# DDS_RIKEN_main.net
KiCad netlist of a schematic drawn in Altium Designer
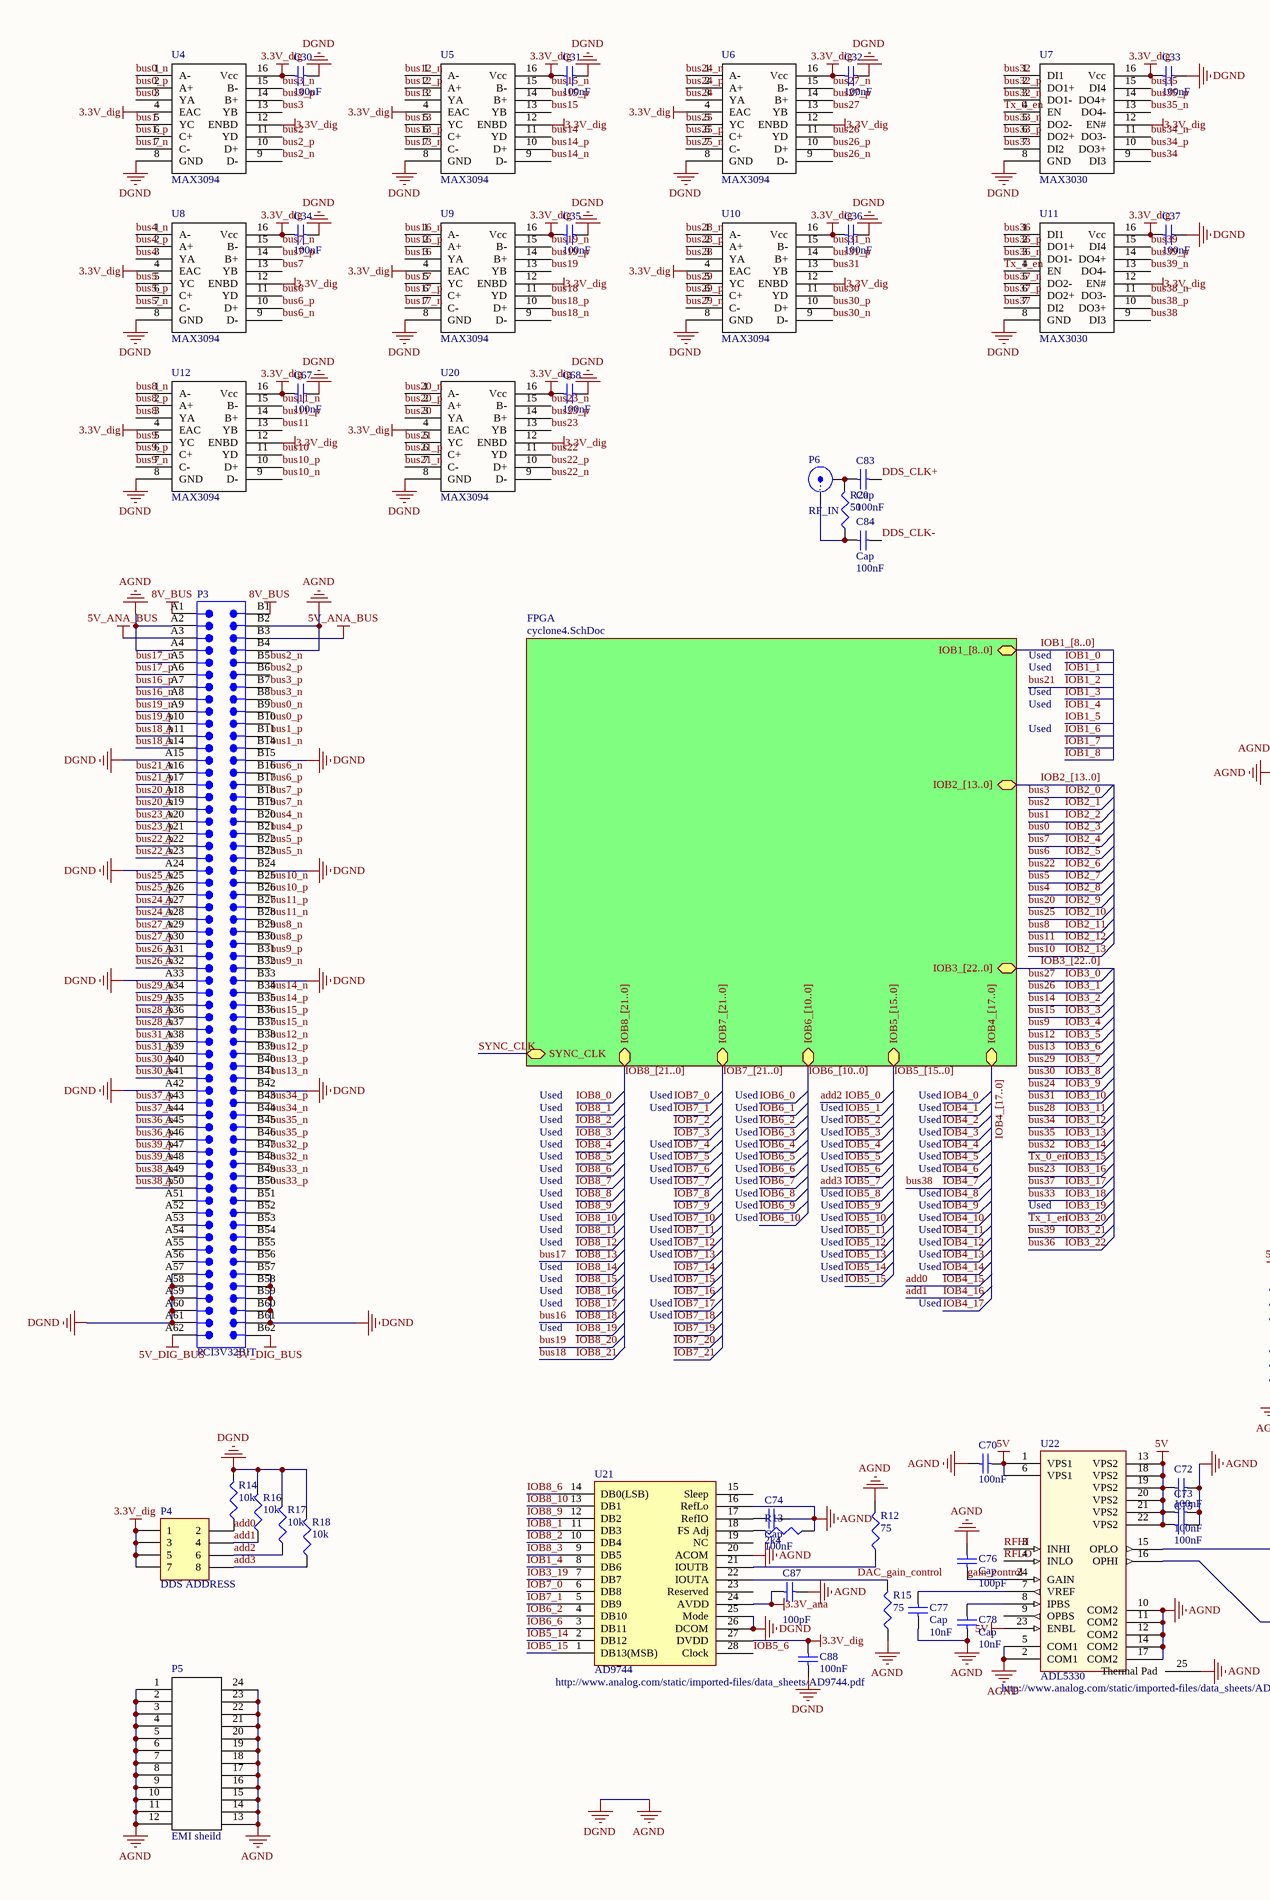
[diagram p0: DDS_RIKEN_main.SchDoc, left]
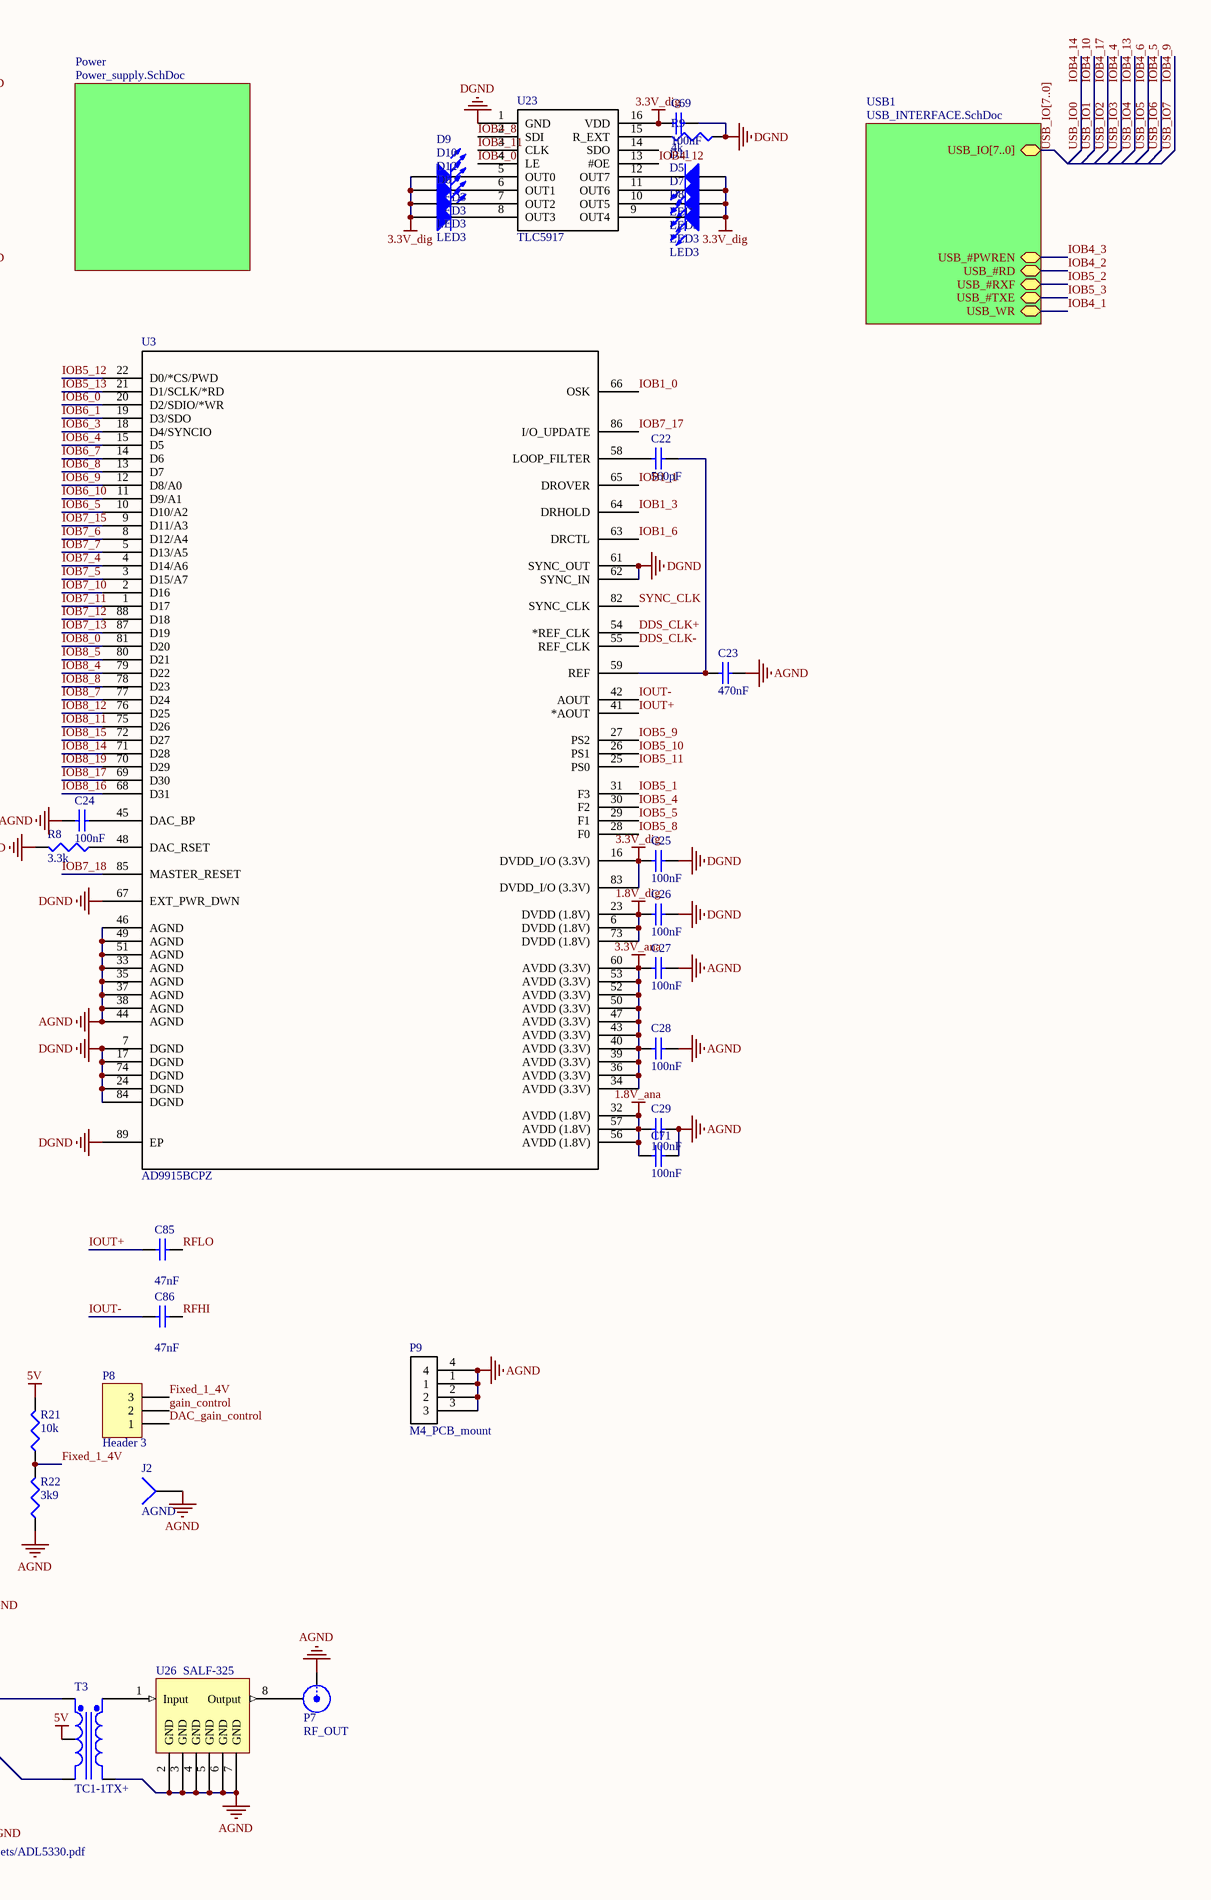
[diagram p1: DDS_RIKEN_main.SchDoc, right]

(export (version "E")
  (design (tool "Eeschema 10.0.6"))
  (components
    (comp (ref "C22")
      (value "560pF")
      (footprint "CAPC2012L")
      (description "Capacitor (Semiconductor SIM Model)")
      (fields (field (name "Comment") "Cap Semi") (field (name "PUBLISHER") "Altium Limited"))
      (libsource (lib "Miscellaneous Devices") (part "Cap Semi"))
    )
    (comp (ref "C23")
      (value "470nF")
      (footprint "CAPC2012L")
      (description "Capacitor (Semiconductor SIM Model)")
      (fields (field (name "Comment") "Cap Semi") (field (name "PUBLISHER") "Altium Limited"))
      (libsource (lib "Miscellaneous Devices") (part "Cap Semi"))
    )
    (comp (ref "C24")
      (value "100nF")
      (footprint "CAPC2012L")
      (description "Capacitor (Semiconductor SIM Model)")
      (fields (field (name "Comment") "Cap Semi") (field (name "PUBLISHER") "Altium Limited"))
      (libsource (lib "Miscellaneous Devices") (part "Cap Semi"))
    )
    (comp (ref "C25")
      (value "100nF")
      (footprint "CAPC2012L")
      (description "Capacitor (Semiconductor SIM Model)")
      (fields (field (name "Comment") "Cap Semi") (field (name "PUBLISHER") "Altium Limited"))
      (libsource (lib "Miscellaneous Devices") (part "Cap Semi"))
    )
    (comp (ref "C26")
      (value "100nF")
      (footprint "CAPC2012L")
      (description "Capacitor (Semiconductor SIM Model)")
      (fields (field (name "Comment") "Cap Semi") (field (name "PUBLISHER") "Altium Limited"))
      (libsource (lib "Miscellaneous Devices") (part "Cap Semi"))
    )
    (comp (ref "C27")
      (value "100nF")
      (footprint "CAPC2012L")
      (description "Capacitor (Semiconductor SIM Model)")
      (fields (field (name "Comment") "Cap Semi") (field (name "PUBLISHER") "Altium Limited"))
      (libsource (lib "Miscellaneous Devices") (part "Cap Semi"))
    )
    (comp (ref "C28")
      (value "100nF")
      (footprint "CAPC2012L")
      (description "Capacitor (Semiconductor SIM Model)")
      (fields (field (name "Comment") "Cap Semi") (field (name "PUBLISHER") "Altium Limited"))
      (libsource (lib "Miscellaneous Devices") (part "Cap Semi"))
    )
    (comp (ref "C29")
      (value "100nF")
      (footprint "CAPC2012L")
      (description "Capacitor (Semiconductor SIM Model)")
      (fields (field (name "Comment") "Cap Semi") (field (name "PUBLISHER") "Altium Limited"))
      (libsource (lib "Miscellaneous Devices") (part "Cap Semi"))
    )
    (comp (ref "C30")
      (value "100nF")
      (footprint "CAPC2012L")
      (description "Capacitor (Semiconductor SIM Model)")
      (fields (field (name "Comment") "Cap Semi") (field (name "PUBLISHER") "Altium Limited"))
      (libsource (lib "Miscellaneous Devices") (part "Cap Semi"))
    )
    (comp (ref "C31")
      (value "100nF")
      (footprint "CAPC2012L")
      (description "Capacitor (Semiconductor SIM Model)")
      (fields (field (name "Comment") "Cap Semi") (field (name "PUBLISHER") "Altium Limited"))
      (libsource (lib "Miscellaneous Devices") (part "Cap Semi"))
    )
    (comp (ref "C32")
      (value "100nF")
      (footprint "CAPC2012L")
      (description "Capacitor (Semiconductor SIM Model)")
      (fields (field (name "Comment") "Cap Semi") (field (name "PUBLISHER") "Altium Limited"))
      (libsource (lib "Miscellaneous Devices") (part "Cap Semi"))
    )
    (comp (ref "C33")
      (value "100nF")
      (footprint "CAPC2012L")
      (description "Capacitor (Semiconductor SIM Model)")
      (fields (field (name "Comment") "Cap Semi") (field (name "PUBLISHER") "Altium Limited"))
      (libsource (lib "Miscellaneous Devices") (part "Cap Semi"))
    )
    (comp (ref "C34")
      (value "100nF")
      (footprint "CAPC2012L")
      (description "Capacitor (Semiconductor SIM Model)")
      (fields (field (name "Comment") "Cap Semi") (field (name "PUBLISHER") "Altium Limited"))
      (libsource (lib "Miscellaneous Devices") (part "Cap Semi"))
    )
    (comp (ref "C35")
      (value "100nF")
      (footprint "CAPC2012L")
      (description "Capacitor (Semiconductor SIM Model)")
      (fields (field (name "Comment") "Cap Semi") (field (name "PUBLISHER") "Altium Limited"))
      (libsource (lib "Miscellaneous Devices") (part "Cap Semi"))
    )
    (comp (ref "C36")
      (value "100nF")
      (footprint "CAPC2012L")
      (description "Capacitor (Semiconductor SIM Model)")
      (fields (field (name "Comment") "Cap Semi") (field (name "PUBLISHER") "Altium Limited"))
      (libsource (lib "Miscellaneous Devices") (part "Cap Semi"))
    )
    (comp (ref "C37")
      (value "100nF")
      (footprint "CAPC2012L")
      (description "Capacitor (Semiconductor SIM Model)")
      (fields (field (name "Comment") "Cap Semi") (field (name "PUBLISHER") "Altium Limited"))
      (libsource (lib "Miscellaneous Devices") (part "Cap Semi"))
    )
    (comp (ref "C67")
      (value "100nF")
      (footprint "CAPC2012L")
      (description "Capacitor (Semiconductor SIM Model)")
      (fields (field (name "Comment") "Cap Semi") (field (name "PUBLISHER") "Altium Limited"))
      (libsource (lib "Miscellaneous Devices") (part "Cap Semi"))
    )
    (comp (ref "C68")
      (value "100nF")
      (footprint "CAPC2012L")
      (description "Capacitor (Semiconductor SIM Model)")
      (fields (field (name "Comment") "Cap Semi") (field (name "PUBLISHER") "Altium Limited"))
      (libsource (lib "Miscellaneous Devices") (part "Cap Semi"))
    )
    (comp (ref "C69")
      (value "100nF")
      (footprint "CAPC2012L")
      (description "Capacitor (Semiconductor SIM Model)")
      (fields (field (name "Comment") "Cap Semi") (field (name "PUBLISHER") "Altium Limited"))
      (libsource (lib "Miscellaneous Devices") (part "Cap Semi"))
    )
    (comp (ref "C70")
      (value "100nF")
      (footprint "CAPC2012L")
      (description "Capacitor (Semiconductor SIM Model)")
      (fields (field (name "Comment") "Cap Semi") (field (name "PUBLISHER") "Altium Limited"))
      (libsource (lib "Miscellaneous Devices") (part "Cap Semi"))
    )
    (comp (ref "C71")
      (value "100nF")
      (footprint "CAPC2012L")
      (description "Capacitor (Semiconductor SIM Model)")
      (fields (field (name "Comment") "Cap Semi") (field (name "PUBLISHER") "Altium Limited"))
      (libsource (lib "Miscellaneous Devices") (part "Cap Semi"))
    )
    (comp (ref "C72")
      (value "100nF")
      (footprint "CAPC2012L")
      (description "Capacitor (Semiconductor SIM Model)")
      (fields (field (name "Comment") "Cap Semi") (field (name "PUBLISHER") "Altium Limited"))
      (libsource (lib "Miscellaneous Devices") (part "Cap Semi"))
    )
    (comp (ref "C73")
      (value "100nF")
      (footprint "CAPC2012L")
      (description "Capacitor (Semiconductor SIM Model)")
      (fields (field (name "Comment") "Cap Semi") (field (name "PUBLISHER") "Altium Limited"))
      (libsource (lib "Miscellaneous Devices") (part "Cap Semi"))
    )
    (comp (ref "C74")
      (value "Cap")
      (footprint "c0805")
      (description "Capacitor")
      (fields
        (field (name "ALTIUM_VALUE") "100nF")
        (field (name "VOLTAGE") "16V")
        (field (name "PUBLISHER") "Altium Limited")
      )
      (libsource (lib "Miscellaneous Devices") (part "Cap"))
    )
    (comp (ref "C75")
      (value "100nF")
      (footprint "CAPC2012L")
      (description "Capacitor (Semiconductor SIM Model)")
      (fields (field (name "Comment") "Cap Semi") (field (name "PUBLISHER") "Altium Limited"))
      (libsource (lib "Miscellaneous Devices") (part "Cap Semi"))
    )
    (comp (ref "C76")
      (value "Cap")
      (footprint "c0805")
      (description "Capacitor")
      (fields
        (field (name "ALTIUM_VALUE") "100pF")
        (field (name "VOLTAGE") "16V")
        (field (name "PUBLISHER") "Altium Limited")
      )
      (libsource (lib "Miscellaneous Devices") (part "Cap"))
    )
    (comp (ref "C77")
      (value "Cap")
      (footprint "c0805")
      (description "Capacitor")
      (fields
        (field (name "ALTIUM_VALUE") "10nF")
        (field (name "VOLTAGE") "16V")
        (field (name "PUBLISHER") "Altium Limited")
      )
      (libsource (lib "Miscellaneous Devices") (part "Cap"))
    )
    (comp (ref "C78")
      (value "Cap")
      (footprint "c0805")
      (description "Capacitor")
      (fields
        (field (name "ALTIUM_VALUE") "10nF")
        (field (name "VOLTAGE") "16V")
        (field (name "PUBLISHER") "Altium Limited")
      )
      (libsource (lib "Miscellaneous Devices") (part "Cap"))
    )
    (comp (ref "C83")
      (value "Cap")
      (footprint "c0805")
      (description "Capacitor")
      (fields
        (field (name "ALTIUM_VALUE") "100nF")
        (field (name "VOLTAGE") "16V")
        (field (name "PUBLISHER") "Altium Limited")
      )
      (libsource (lib "Miscellaneous Devices") (part "Cap"))
    )
    (comp (ref "C84")
      (value "Cap")
      (footprint "c0805")
      (description "Capacitor")
      (fields
        (field (name "ALTIUM_VALUE") "100nF")
        (field (name "VOLTAGE") "16V")
        (field (name "PUBLISHER") "Altium Limited")
      )
      (libsource (lib "Miscellaneous Devices") (part "Cap"))
    )
    (comp (ref "C85")
      (value "47nF")
      (footprint "c0805")
      (description "Capacitor")
      (fields
        (field (name "VOLTAGE") "16V")
        (field (name "Comment") "Cap")
        (field (name "PUBLISHER") "Altium Limited")
      )
      (libsource (lib "Miscellaneous Devices") (part "Cap"))
    )
    (comp (ref "C86")
      (value "47nF")
      (footprint "c0805")
      (description "Capacitor")
      (fields
        (field (name "VOLTAGE") "16V")
        (field (name "Comment") "Cap")
        (field (name "PUBLISHER") "Altium Limited")
      )
      (libsource (lib "Miscellaneous Devices") (part "Cap"))
    )
    (comp (ref "C87")
      (value "100pF")
      (footprint "c0805")
      (description "Capacitor")
      (fields
        (field (name "VOLTAGE") "16V")
        (field (name "Comment") "Cap")
        (field (name "PUBLISHER") "Altium Limited")
      )
      (libsource (lib "Miscellaneous Devices") (part "Cap"))
    )
    (comp (ref "C88")
      (value "100nF")
      (footprint "c0805")
      (description "Capacitor")
      (fields
        (field (name "VOLTAGE") "16V")
        (field (name "Comment") "Cap")
        (field (name "PUBLISHER") "Altium Limited")
      )
      (libsource (lib "Miscellaneous Devices") (part "Cap"))
    )
    (comp (ref "D5")
      (value "LED3")
      (footprint "DSO-C2/D5.6")
      (description "Typical BLUE SiC LED")
      (fields (field (name "PUBLISHER") "Altium Limited"))
      (libsource (lib "Miscellaneous Devices") (part "LED3"))
    )
    (comp (ref "D6")
      (value "LED3")
      (footprint "DSO-C2/D5.6")
      (description "Typical BLUE SiC LED")
      (fields (field (name "PUBLISHER") "Altium Limited"))
      (libsource (lib "Miscellaneous Devices") (part "LED3"))
    )
    (comp (ref "D7")
      (value "LED3")
      (footprint "DSO-C2/D5.6")
      (description "Typical BLUE SiC LED")
      (fields (field (name "PUBLISHER") "Altium Limited"))
      (libsource (lib "Miscellaneous Devices") (part "LED3"))
    )
    (comp (ref "D8")
      (value "LED3")
      (footprint "DSO-C2/D5.6")
      (description "Typical BLUE SiC LED")
      (fields (field (name "PUBLISHER") "Altium Limited"))
      (libsource (lib "Miscellaneous Devices") (part "LED3"))
    )
    (comp (ref "D9")
      (value "LED3")
      (footprint "DSO-C2/D5.6")
      (description "Typical BLUE SiC LED")
      (fields (field (name "PUBLISHER") "Altium Limited"))
      (libsource (lib "Miscellaneous Devices") (part "LED3"))
    )
    (comp (ref "D10")
      (value "LED3")
      (footprint "DSO-C2/D5.6")
      (description "Typical BLUE SiC LED")
      (fields (field (name "PUBLISHER") "Altium Limited"))
      (libsource (lib "Miscellaneous Devices") (part "LED3"))
    )
    (comp (ref "D11")
      (value "LED3")
      (footprint "DSO-C2/D5.6")
      (description "Typical BLUE SiC LED")
      (fields (field (name "PUBLISHER") "Altium Limited"))
      (libsource (lib "Miscellaneous Devices") (part "LED3"))
    )
    (comp (ref "D12")
      (value "LED3")
      (footprint "DSO-C2/D5.6")
      (description "Typical BLUE SiC LED")
      (fields (field (name "PUBLISHER") "Altium Limited"))
      (libsource (lib "Miscellaneous Devices") (part "LED3"))
    )
    (comp (ref "J2")
      (value "AGND")
      (footprint "PIN1")
      (description "Socket")
      (fields (field (name "PUBLISHER") "Altium Limited"))
      (libsource (lib "Miscellaneous Connectors") (part "Socket"))
    )
    (comp (ref "P3")
      (value "PCI3V32BIT")
      (footprint "PCI3V32BIT")
      (description "Card, 120-Position")
      (libsource (lib "*") (part "PCI3V32BIT"))
    )
    (comp (ref "P4")
      (value "DDS ADDRESS")
      (footprint "HDR2X4")
      (description "Header, 4-Pin, Dual row")
      (fields (field (name "PUBLISHER") "Altium Limited"))
      (libsource (lib "Miscellaneous Connectors") (part "Header 4X2"))
    )
    (comp (ref "P5")
      (value "EMI sheild")
      (footprint "BMIS-207")
      (description "Laird Shield")
      (fields (field (name "PUBLISHER") "Altium Limited"))
      (libsource (lib "HH_chips") (part "BMIS-207"))
    )
    (comp (ref "P6")
      (value "RF_IN")
      (footprint "SMA_Edgecon_31milthick")
      (description "SMA Straight Connector")
      (fields (field (name "PUBLISHER") "Altium Limited"))
      (libsource (lib "Miscellaneous Connectors") (part "SMB"))
    )
    (comp (ref "P7")
      (value "RF_OUT")
      (footprint "SMA_Edgecon_31milthick")
      (description "SMA Straight Connector")
      (fields (field (name "PUBLISHER") "Altium Limited"))
      (libsource (lib "Miscellaneous Connectors") (part "SMB"))
    )
    (comp (ref "P8")
      (value "Header 3")
      (footprint "HDR1X3")
      (description "Header, 3-Pin")
      (fields (field (name "PUBLISHER") "Altium Limited"))
      (libsource (lib "Miscellaneous Connectors") (part "Header 3"))
    )
    (comp (ref "P9")
      (value "M4_PCB_mount")
      (footprint "M4_PCB_mount")
      (libsource (lib "HH_chips") (part "M4_PCB_mount"))
    )
    (comp (ref "R8")
      (value "3.3k")
      (footprint "RESC3216L")
      (description "Resistor")
      (fields (field (name "PUBLISHER") "Altium Limited"))
      (libsource (lib "Miscellaneous Devices") (part "Res3"))
    )
    (comp (ref "R9")
      (value "4k")
      (footprint "RESC3216L")
      (description "Resistor")
      (fields (field (name "PUBLISHER") "Altium Limited"))
      (libsource (lib "Miscellaneous Devices") (part "Res3"))
    )
    (comp (ref "R12")
      (value "75")
      (footprint "RESC3216L")
      (description "Resistor")
      (fields (field (name "PUBLISHER") "Altium Limited"))
      (libsource (lib "Miscellaneous Devices") (part "Res3"))
    )
    (comp (ref "R13")
      (value "2k4")
      (footprint "RESC3216L")
      (description "Resistor")
      (fields (field (name "PUBLISHER") "Altium Limited"))
      (libsource (lib "Miscellaneous Devices") (part "Res3"))
    )
    (comp (ref "R14")
      (value "10k")
      (footprint "RESC3216L")
      (description "Resistor")
      (fields (field (name "PUBLISHER") "Altium Limited"))
      (libsource (lib "Miscellaneous Devices") (part "Res3"))
    )
    (comp (ref "R15")
      (value "75")
      (footprint "RESC3216L")
      (description "Resistor")
      (fields (field (name "PUBLISHER") "Altium Limited"))
      (libsource (lib "Miscellaneous Devices") (part "Res3"))
    )
    (comp (ref "R16")
      (value "10k")
      (footprint "RESC3216L")
      (description "Resistor")
      (fields (field (name "PUBLISHER") "Altium Limited"))
      (libsource (lib "Miscellaneous Devices") (part "Res3"))
    )
    (comp (ref "R17")
      (value "10k")
      (footprint "RESC3216L")
      (description "Resistor")
      (fields (field (name "PUBLISHER") "Altium Limited"))
      (libsource (lib "Miscellaneous Devices") (part "Res3"))
    )
    (comp (ref "R18")
      (value "10k")
      (footprint "RESC3216L")
      (description "Resistor")
      (fields (field (name "PUBLISHER") "Altium Limited"))
      (libsource (lib "Miscellaneous Devices") (part "Res3"))
    )
    (comp (ref "R20")
      (value "50")
      (footprint "RESC3216L")
      (description "Resistor")
      (fields (field (name "PUBLISHER") "Altium Limited"))
      (libsource (lib "Miscellaneous Devices") (part "Res3"))
    )
    (comp (ref "R21")
      (value "10k")
      (footprint "RESC3216L")
      (description "Resistor")
      (fields (field (name "PUBLISHER") "Altium Limited"))
      (libsource (lib "Miscellaneous Devices") (part "Res3"))
    )
    (comp (ref "R22")
      (value "3k9")
      (footprint "RESC3216L")
      (description "Resistor")
      (fields (field (name "PUBLISHER") "Altium Limited"))
      (libsource (lib "Miscellaneous Devices") (part "Res3"))
    )
    (comp (ref "T3")
      (value "TC1-1TX+")
      (footprint "TC1-1T+")
      (description "Center-Tapped Transformer (Coupled Inductor Model)")
      (fields (field (name "PUBLISHER") "Altium Limited"))
      (libsource (lib "Miscellaneous Devices") (part "Trans CT"))
    )
    (comp (ref "U3")
      (value "AD9915BCPZ")
      (footprint "CP_88_5")
      (description "Imported")
      (libsource (lib "2014-10-16_14-30-18") (part "AD9915BCPZ"))
    )
    (comp (ref "U4")
      (value "MAX3094")
      (footprint "TSSOP16")
      (description "Differential Line Receivers")
      (libsource (lib "HH_chips") (part "MAX3094"))
    )
    (comp (ref "U5")
      (value "MAX3094")
      (footprint "TSSOP16")
      (description "Differential Line Receivers")
      (libsource (lib "HH_chips") (part "MAX3094"))
    )
    (comp (ref "U6")
      (value "MAX3094")
      (footprint "TSSOP16")
      (description "Differential Line Receivers")
      (libsource (lib "HH_chips") (part "MAX3094"))
    )
    (comp (ref "U7")
      (value "MAX3030")
      (footprint "TSSOP16")
      (description "Differential Line Transmitter")
      (libsource (lib "HH_chips") (part "MAX3030"))
    )
    (comp (ref "U8")
      (value "MAX3094")
      (footprint "TSSOP16")
      (description "Differential Line Receivers")
      (libsource (lib "HH_chips") (part "MAX3094"))
    )
    (comp (ref "U9")
      (value "MAX3094")
      (footprint "TSSOP16")
      (description "Differential Line Receivers")
      (libsource (lib "HH_chips") (part "MAX3094"))
    )
    (comp (ref "U10")
      (value "MAX3094")
      (footprint "TSSOP16")
      (description "Differential Line Receivers")
      (libsource (lib "HH_chips") (part "MAX3094"))
    )
    (comp (ref "U11")
      (value "MAX3030")
      (footprint "TSSOP16")
      (description "Differential Line Transmitter")
      (libsource (lib "HH_chips") (part "MAX3030"))
    )
    (comp (ref "U12")
      (value "MAX3094")
      (footprint "TSSOP16")
      (description "Differential Line Receivers")
      (libsource (lib "HH_chips") (part "MAX3094"))
    )
    (comp (ref "U20")
      (value "MAX3094")
      (footprint "TSSOP16")
      (description "Differential Line Receivers")
      (libsource (lib "HH_chips") (part "MAX3094"))
    )
    (comp (ref "U21")
      (value "AD9744")
      (footprint "TSOP65P640-28AM")
      (fields (field (name "HELPURL") "http://www.analog.com/static/imported-files/data_sheets/AD9744.pdf"))
      (libsource (lib "eigene") (part "AD9744"))
    )
    (comp (ref "U22")
      (value "ADL5330")
      (footprint "QFN50P400X400-24VAN")
      (description "analoger Abschwächer")
      (fields (field (name "HELPURL") "http://www.analog.com/static/imported-files/data_sheets/ADL5330.pdf"))
      (libsource (lib "eigene") (part "ADL5330"))
    )
    (comp (ref "U23")
      (value "TLC5917")
      (footprint "D016_N")
      (description "8-bit LED driver (Serial)")
      (libsource (lib "HH_chips") (part "TLC5917"))
    )
    (comp (ref "U26")
      (value "SALF-325")
      (footprint "SALF-325")
      (libsource (lib "Mini-Circuits") (part "SALF-325"))
    )
  )
  (nets
    (net (code "1") (name "/DAC_gain_control") (class "Default")
      (node (ref "P8") (pin "1") (pinfunction "1_1") (pintype "passive"))
      (node (ref "R15") (pin "2") (pinfunction "2_2") (pintype "passive"))
      (node (ref "U21") (pin "22") (pinfunction "IOUTA_22") (pintype "power_in"))
    )
    (net (code "2") (name "/DDS_CLK+") (class "Default")
      (node (ref "C83") (pin "1") (pinfunction "1_1") (pintype "passive"))
      (node (ref "U3") (pin "54") (pinfunction "*REF_CLK_54") (pintype "passive"))
    )
    (net (code "3") (name "/DDS_CLK-") (class "Default")
      (node (ref "C84") (pin "1") (pinfunction "1_1") (pintype "passive"))
      (node (ref "U3") (pin "55") (pinfunction "REF_CLK_55") (pintype "passive"))
    )
    (net (code "4") (name "/Fixed_1_4V") (class "Default")
      (node (ref "P8") (pin "3") (pinfunction "3_3") (pintype "passive"))
      (node (ref "R21") (pin "1") (pinfunction "1_1") (pintype "passive"))
      (node (ref "R22") (pin "2") (pinfunction "2_2") (pintype "passive"))
    )
    (net (code "5") (name "/IOB1_0") (class "Default")
      (node (ref "U3") (pin "66") (pinfunction "OSK_66") (pintype "passive"))
    )
    (net (code "6") (name "/IOB1_1") (class "Default")
      (node (ref "U3") (pin "65") (pinfunction "DROVER_65") (pintype "passive"))
    )
    (net (code "7") (name "/IOB1_2") (class "Default")
      (node (ref "U20") (pin "5") (pinfunction "YC_5") (pintype "passive"))
    )
    (net (code "8") (name "/IOB1_3") (class "Default")
      (node (ref "U3") (pin "64") (pinfunction "DRHOLD_64") (pintype "passive"))
    )
    (net (code "9") (name "/IOB1_4") (class "Default")
      (node (ref "U21") (pin "8") (pinfunction "DB6_8") (pintype "power_in"))
    )
    (net (code "11") (name "/IOB1_6") (class "Default")
      (node (ref "U3") (pin "63") (pinfunction "DRCTL_63") (pintype "passive"))
    )
    (net (code "15") (name "/IOB2_0") (class "Default")
      (node (ref "U4") (pin "13") (pinfunction "YB_13") (pintype "passive"))
    )
    (net (code "16") (name "/IOB2_1") (class "Default")
      (node (ref "U4") (pin "11") (pinfunction "YD_11") (pintype "passive"))
    )
    (net (code "17") (name "/IOB2_2") (class "Default")
      (node (ref "U4") (pin "5") (pinfunction "YC_5") (pintype "passive"))
    )
    (net (code "18") (name "/IOB2_3") (class "Default")
      (node (ref "U4") (pin "3") (pinfunction "YA_3") (pintype "passive"))
    )
    (net (code "19") (name "/IOB2_4") (class "Default")
      (node (ref "U8") (pin "13") (pinfunction "YB_13") (pintype "passive"))
    )
    (net (code "20") (name "/IOB2_5") (class "Default")
      (node (ref "U8") (pin "11") (pinfunction "YD_11") (pintype "passive"))
    )
    (net (code "21") (name "/IOB2_6") (class "Default")
      (node (ref "U20") (pin "11") (pinfunction "YD_11") (pintype "passive"))
    )
    (net (code "22") (name "/IOB2_7") (class "Default")
      (node (ref "U8") (pin "5") (pinfunction "YC_5") (pintype "passive"))
    )
    (net (code "23") (name "/IOB2_8") (class "Default")
      (node (ref "U8") (pin "3") (pinfunction "YA_3") (pintype "passive"))
    )
    (net (code "24") (name "/IOB2_9") (class "Default")
      (node (ref "U20") (pin "3") (pinfunction "YA_3") (pintype "passive"))
    )
    (net (code "25") (name "/IOB2_10") (class "Default")
      (node (ref "U6") (pin "5") (pinfunction "YC_5") (pintype "passive"))
    )
    (net (code "26") (name "/IOB2_11") (class "Default")
      (node (ref "U12") (pin "3") (pinfunction "YA_3") (pintype "passive"))
    )
    (net (code "27") (name "/IOB2_12") (class "Default")
      (node (ref "U12") (pin "13") (pinfunction "YB_13") (pintype "passive"))
    )
    (net (code "28") (name "/IOB2_13") (class "Default")
      (node (ref "U12") (pin "11") (pinfunction "YD_11") (pintype "passive"))
    )
    (net (code "30") (name "/IOB3_0") (class "Default")
      (node (ref "U6") (pin "13") (pinfunction "YB_13") (pintype "passive"))
    )
    (net (code "31") (name "/IOB3_1") (class "Default")
      (node (ref "U6") (pin "11") (pinfunction "YD_11") (pintype "passive"))
    )
    (net (code "32") (name "/IOB3_2") (class "Default")
      (node (ref "U5") (pin "11") (pinfunction "YD_11") (pintype "passive"))
    )
    (net (code "33") (name "/IOB3_3") (class "Default")
      (node (ref "U5") (pin "13") (pinfunction "YB_13") (pintype "passive"))
    )
    (net (code "34") (name "/IOB3_4") (class "Default")
      (node (ref "U12") (pin "5") (pinfunction "YC_5") (pintype "passive"))
    )
    (net (code "35") (name "/IOB3_5") (class "Default")
      (node (ref "U5") (pin "3") (pinfunction "YA_3") (pintype "passive"))
    )
    (net (code "36") (name "/IOB3_6") (class "Default")
      (node (ref "U5") (pin "5") (pinfunction "YC_5") (pintype "passive"))
    )
    (net (code "37") (name "/IOB3_7") (class "Default")
      (node (ref "U10") (pin "5") (pinfunction "YC_5") (pintype "passive"))
    )
    (net (code "38") (name "/IOB3_8") (class "Default")
      (node (ref "U10") (pin "11") (pinfunction "YD_11") (pintype "passive"))
    )
    (net (code "39") (name "/IOB3_9") (class "Default")
      (node (ref "U6") (pin "3") (pinfunction "YA_3") (pintype "passive"))
    )
    (net (code "40") (name "/IOB3_10") (class "Default")
      (node (ref "U10") (pin "13") (pinfunction "YB_13") (pintype "passive"))
    )
    (net (code "41") (name "/IOB3_11") (class "Default")
      (node (ref "U10") (pin "3") (pinfunction "YA_3") (pintype "passive"))
    )
    (net (code "42") (name "/IOB3_12") (class "Default")
      (node (ref "U7") (pin "9") (pinfunction "DI3_9") (pintype "passive"))
    )
    (net (code "43") (name "/IOB3_13") (class "Default")
      (node (ref "U7") (pin "15") (pinfunction "DI4_15") (pintype "passive"))
    )
    (net (code "44") (name "/IOB3_14") (class "Default")
      (node (ref "U7") (pin "1") (pinfunction "DI1_1") (pintype "passive"))
    )
    (net (code "45") (name "/IOB3_15") (class "Default")
      (node (ref "U7") (pin "4") (pinfunction "EN_4") (pintype "passive"))
    )
    (net (code "46") (name "/IOB3_16") (class "Default")
      (node (ref "U20") (pin "13") (pinfunction "YB_13") (pintype "passive"))
    )
    (net (code "47") (name "/IOB3_17") (class "Default")
      (node (ref "U11") (pin "7") (pinfunction "DI2_7") (pintype "passive"))
    )
    (net (code "48") (name "/IOB3_18") (class "Default")
      (node (ref "U7") (pin "7") (pinfunction "DI2_7") (pintype "passive"))
    )
    (net (code "49") (name "/IOB3_19") (class "Default")
      (node (ref "U21") (pin "7") (pinfunction "DB7_7") (pintype "power_in"))
    )
    (net (code "50") (name "/IOB3_20") (class "Default")
      (node (ref "U11") (pin "4") (pinfunction "EN_4") (pintype "passive"))
    )
    (net (code "51") (name "/IOB3_21") (class "Default")
      (node (ref "U11") (pin "15") (pinfunction "DI4_15") (pintype "passive"))
    )
    (net (code "52") (name "/IOB3_22") (class "Default")
      (node (ref "U11") (pin "1") (pinfunction "DI1_1") (pintype "passive"))
    )
    (net (code "54") (name "/IOB4_0") (class "Default")
      (node (ref "U23") (pin "4") (pinfunction "LE_4") (pintype "passive"))
    )
    (net (code "58") (name "/IOB4_7") (class "Default")
      (node (ref "U11") (pin "9") (pinfunction "DI3_9") (pintype "passive"))
    )
    (net (code "59") (name "/IOB4_8") (class "Default")
      (node (ref "U23") (pin "2") (pinfunction "SDI_2") (pintype "passive"))
    )
    (net (code "60") (name "/IOB4_11") (class "Default")
      (node (ref "U23") (pin "3") (pinfunction "CLK_3") (pintype "passive"))
    )
    (net (code "61") (name "/IOB4_12") (class "Default")
      (node (ref "U23") (pin "13") (pinfunction "#OE_13") (pintype "passive"))
    )
    (net (code "62") (name "/IOB4_15") (class "Default")
      (node (ref "P4") (pin "2") (pinfunction "2_2") (pintype "passive"))
      (node (ref "R14") (pin "1") (pinfunction "1_1") (pintype "passive"))
    )
    (net (code "63") (name "/IOB4_16") (class "Default")
      (node (ref "P4") (pin "4") (pinfunction "4_4") (pintype "passive"))
      (node (ref "R16") (pin "1") (pinfunction "1_1") (pintype "passive"))
    )
    (net (code "65") (name "/IOB5_0") (class "Default")
      (node (ref "P4") (pin "6") (pinfunction "6_6") (pintype "passive"))
      (node (ref "R17") (pin "1") (pinfunction "1_1") (pintype "passive"))
    )
    (net (code "66") (name "/IOB5_1") (class "Default")
      (node (ref "U3") (pin "31") (pinfunction "F3_31") (pintype "passive"))
    )
    (net (code "69") (name "/IOB5_4") (class "Default")
      (node (ref "U3") (pin "30") (pinfunction "F2_30") (pintype "passive"))
    )
    (net (code "70") (name "/IOB5_5") (class "Default")
      (node (ref "U3") (pin "29") (pinfunction "F1_29") (pintype "passive"))
    )
    (net (code "71") (name "/IOB5_6") (class "Default")
      (node (ref "U21") (pin "28") (pinfunction "Clock_28") (pintype "power_in"))
    )
    (net (code "72") (name "/IOB5_7") (class "Default")
      (node (ref "P4") (pin "8") (pinfunction "8_8") (pintype "passive"))
      (node (ref "R18") (pin "1") (pinfunction "1_1") (pintype "passive"))
    )
    (net (code "73") (name "/IOB5_8") (class "Default")
      (node (ref "U3") (pin "28") (pinfunction "F0_28") (pintype "passive"))
    )
    (net (code "74") (name "/IOB5_9") (class "Default")
      (node (ref "U3") (pin "27") (pinfunction "PS2_27") (pintype "passive"))
    )
    (net (code "75") (name "/IOB5_10") (class "Default")
      (node (ref "U3") (pin "26") (pinfunction "PS1_26") (pintype "passive"))
    )
    (net (code "76") (name "/IOB5_11") (class "Default")
      (node (ref "U3") (pin "25") (pinfunction "PS0_25") (pintype "passive"))
    )
    (net (code "77") (name "/IOB5_12") (class "Default")
      (node (ref "U3") (pin "22") (pinfunction "D0/*CS/PWD_22") (pintype "passive"))
    )
    (net (code "78") (name "/IOB5_13") (class "Default")
      (node (ref "U3") (pin "21") (pinfunction "D1/SCLK/*RD_21") (pintype "passive"))
    )
    (net (code "79") (name "/IOB5_14") (class "Default")
      (node (ref "U21") (pin "2") (pinfunction "DB12_2") (pintype "power_in"))
    )
    (net (code "80") (name "/IOB5_15") (class "Default")
      (node (ref "U21") (pin "1") (pinfunction "DB13(MSB)_1") (pintype "power_in"))
    )
    (net (code "82") (name "/IOB6_0") (class "Default")
      (node (ref "U3") (pin "20") (pinfunction "D2/SDIO/*WR_20") (pintype "passive"))
    )
    (net (code "83") (name "/IOB6_1") (class "Default")
      (node (ref "U3") (pin "19") (pinfunction "D3/SDO_19") (pintype "passive"))
    )
    (net (code "84") (name "/IOB6_2") (class "Default")
      (node (ref "U21") (pin "4") (pinfunction "DB10_4") (pintype "power_in"))
    )
    (net (code "85") (name "/IOB6_3") (class "Default")
      (node (ref "U3") (pin "18") (pinfunction "D4/SYNCIO_18") (pintype "passive"))
    )
    (net (code "86") (name "/IOB6_4") (class "Default")
      (node (ref "U3") (pin "15") (pinfunction "D5_15") (pintype "passive"))
    )
    (net (code "87") (name "/IOB6_5") (class "Default")
      (node (ref "U3") (pin "10") (pinfunction "D10/A2_10") (pintype "passive"))
    )
    (net (code "88") (name "/IOB6_6") (class "Default")
      (node (ref "U21") (pin "3") (pinfunction "DB11_3") (pintype "power_in"))
    )
    (net (code "89") (name "/IOB6_7") (class "Default")
      (node (ref "U3") (pin "14") (pinfunction "D6_14") (pintype "passive"))
    )
    (net (code "90") (name "/IOB6_8") (class "Default")
      (node (ref "U3") (pin "13") (pinfunction "D7_13") (pintype "passive"))
    )
    (net (code "91") (name "/IOB6_9") (class "Default")
      (node (ref "U3") (pin "12") (pinfunction "D8/A0_12") (pintype "passive"))
    )
    (net (code "92") (name "/IOB6_10") (class "Default")
      (node (ref "U3") (pin "11") (pinfunction "D9/A1_11") (pintype "passive"))
    )
    (net (code "94") (name "/IOB7_0") (class "Default")
      (node (ref "U21") (pin "6") (pinfunction "DB8_6") (pintype "power_in"))
    )
    (net (code "95") (name "/IOB7_1") (class "Default")
      (node (ref "U21") (pin "5") (pinfunction "DB9_5") (pintype "power_in"))
    )
    (net (code "98") (name "/IOB7_4") (class "Default")
      (node (ref "U3") (pin "4") (pinfunction "D14/A6_4") (pintype "passive"))
    )
    (net (code "99") (name "/IOB7_5") (class "Default")
      (node (ref "U3") (pin "3") (pinfunction "D15/A7_3") (pintype "passive"))
    )
    (net (code "100") (name "/IOB7_6") (class "Default")
      (node (ref "U3") (pin "8") (pinfunction "D12/A4_8") (pintype "passive"))
    )
    (net (code "101") (name "/IOB7_7") (class "Default")
      (node (ref "U3") (pin "5") (pinfunction "D13/A5_5") (pintype "passive"))
    )
    (net (code "104") (name "/IOB7_10") (class "Default")
      (node (ref "U3") (pin "2") (pinfunction "D16_2") (pintype "passive"))
    )
    (net (code "105") (name "/IOB7_11") (class "Default")
      (node (ref "U3") (pin "1") (pinfunction "D17_1") (pintype "passive"))
    )
    (net (code "106") (name "/IOB7_12") (class "Default")
      (node (ref "U3") (pin "88") (pinfunction "D18_88") (pintype "passive"))
    )
    (net (code "107") (name "/IOB7_13") (class "Default")
      (node (ref "U3") (pin "87") (pinfunction "D19_87") (pintype "passive"))
    )
    (net (code "109") (name "/IOB7_15") (class "Default")
      (node (ref "U3") (pin "9") (pinfunction "D11/A3_9") (pintype "passive"))
    )
    (net (code "111") (name "/IOB7_17") (class "Default")
      (node (ref "U3") (pin "86") (pinfunction "I/O_UPDATE_86") (pintype "passive"))
    )
    (net (code "112") (name "/IOB7_18") (class "Default")
      (node (ref "U3") (pin "85") (pinfunction "MASTER_RESET_85") (pintype "passive"))
    )
    (net (code "117") (name "/IOB8_0") (class "Default")
      (node (ref "U3") (pin "81") (pinfunction "D20_81") (pintype "passive"))
    )
    (net (code "118") (name "/IOB8_1") (class "Default")
      (node (ref "U21") (pin "11") (pinfunction "DB3_11") (pintype "power_in"))
    )
    (net (code "119") (name "/IOB8_2") (class "Default")
      (node (ref "U21") (pin "10") (pinfunction "DB4_10") (pintype "power_in"))
    )
    (net (code "120") (name "/IOB8_3") (class "Default")
      (node (ref "U21") (pin "9") (pinfunction "DB5_9") (pintype "power_in"))
    )
    (net (code "121") (name "/IOB8_4") (class "Default")
      (node (ref "U3") (pin "79") (pinfunction "D22_79") (pintype "passive"))
    )
    (net (code "122") (name "/IOB8_5") (class "Default")
      (node (ref "U3") (pin "80") (pinfunction "D21_80") (pintype "passive"))
    )
    (net (code "123") (name "/IOB8_6") (class "Default")
      (node (ref "U21") (pin "14") (pinfunction "DB0(LSB)_14") (pintype "power_in"))
    )
    (net (code "124") (name "/IOB8_7") (class "Default")
      (node (ref "U3") (pin "77") (pinfunction "D24_77") (pintype "passive"))
    )
    (net (code "125") (name "/IOB8_8") (class "Default")
      (node (ref "U3") (pin "78") (pinfunction "D23_78") (pintype "passive"))
    )
    (net (code "126") (name "/IOB8_9") (class "Default")
      (node (ref "U21") (pin "12") (pinfunction "DB2_12") (pintype "power_in"))
    )
    (net (code "127") (name "/IOB8_10") (class "Default")
      (node (ref "U21") (pin "13") (pinfunction "DB1_13") (pintype "power_in"))
    )
    (net (code "128") (name "/IOB8_11") (class "Default")
      (node (ref "U3") (pin "75") (pinfunction "D26_75") (pintype "passive"))
    )
    (net (code "129") (name "/IOB8_12") (class "Default")
      (node (ref "U3") (pin "76") (pinfunction "D25_76") (pintype "passive"))
    )
    (net (code "130") (name "/IOB8_13") (class "Default")
      (node (ref "U9") (pin "5") (pinfunction "YC_5") (pintype "passive"))
    )
    (net (code "131") (name "/IOB8_14") (class "Default")
      (node (ref "U3") (pin "71") (pinfunction "D28_71") (pintype "passive"))
    )
    (net (code "132") (name "/IOB8_15") (class "Default")
      (node (ref "U3") (pin "72") (pinfunction "D27_72") (pintype "passive"))
    )
    (net (code "133") (name "/IOB8_16") (class "Default")
      (node (ref "U3") (pin "68") (pinfunction "D31_68") (pintype "passive"))
    )
    (net (code "134") (name "/IOB8_17") (class "Default")
      (node (ref "U3") (pin "69") (pinfunction "D30_69") (pintype "passive"))
    )
    (net (code "135") (name "/IOB8_18") (class "Default")
      (node (ref "U9") (pin "3") (pinfunction "YA_3") (pintype "passive"))
    )
    (net (code "136") (name "/IOB8_19") (class "Default")
      (node (ref "U3") (pin "70") (pinfunction "D29_70") (pintype "passive"))
    )
    (net (code "137") (name "/IOB8_20") (class "Default")
      (node (ref "U9") (pin "13") (pinfunction "YB_13") (pintype "passive"))
    )
    (net (code "138") (name "/IOB8_21") (class "Default")
      (node (ref "U9") (pin "11") (pinfunction "YD_11") (pintype "passive"))
    )
    (net (code "140") (name "/IOUT+") (class "Default")
      (node (ref "C85") (pin "2") (pinfunction "2_2") (pintype "passive"))
      (node (ref "U3") (pin "41") (pinfunction "*AOUT_41") (pintype "passive"))
    )
    (net (code "141") (name "/IOUT-") (class "Default")
      (node (ref "C86") (pin "2") (pinfunction "2_2") (pintype "passive"))
      (node (ref "U3") (pin "42") (pinfunction "AOUT_42") (pintype "passive"))
    )
    (net (code "142") (name "/RFHI") (class "Default")
      (node (ref "C86") (pin "1") (pinfunction "1_1") (pintype "passive"))
      (node (ref "U22") (pin "3") (pinfunction "INHI_3") (pintype "input"))
    )
    (net (code "143") (name "/RFLO") (class "Default")
      (node (ref "C85") (pin "1") (pinfunction "1_1") (pintype "passive"))
      (node (ref "U22") (pin "4") (pinfunction "INLO_4") (pintype "input"))
    )
    (net (code "144") (name "/SYNC_CLK") (class "Default")
      (node (ref "U3") (pin "82") (pinfunction "SYNC_CLK_82") (pintype "passive"))
    )
    (net (code "154") (name "/bus0_n") (class "Default")
      (node (ref "P3") (pin "B9") (pinfunction "B9_B9") (pintype "passive"))
      (node (ref "U4") (pin "1") (pinfunction "A-_1") (pintype "passive"))
    )
    (net (code "155") (name "/bus0_p") (class "Default")
      (node (ref "P3") (pin "B10") (pinfunction "B10_B10") (pintype "passive"))
      (node (ref "U4") (pin "2") (pinfunction "A+_2") (pintype "passive"))
    )
    (net (code "156") (name "/bus1_n") (class "Default")
      (node (ref "P3") (pin "B14") (pinfunction "B14_B14") (pintype "passive"))
      (node (ref "U4") (pin "7") (pinfunction "C-_7") (pintype "passive"))
    )
    (net (code "157") (name "/bus1_p") (class "Default")
      (node (ref "P3") (pin "B11") (pinfunction "B11_B11") (pintype "passive"))
      (node (ref "U4") (pin "6") (pinfunction "C+_6") (pintype "passive"))
    )
    (net (code "158") (name "/bus2_n") (class "Default")
      (node (ref "P3") (pin "B5") (pinfunction "B5_B5") (pintype "passive"))
      (node (ref "U4") (pin "9") (pinfunction "D-_9") (pintype "passive"))
    )
    (net (code "159") (name "/bus2_p") (class "Default")
      (node (ref "P3") (pin "B6") (pinfunction "B6_B6") (pintype "passive"))
      (node (ref "U4") (pin "10") (pinfunction "D+_10") (pintype "passive"))
    )
    (net (code "160") (name "/bus3_n") (class "Default")
      (node (ref "P3") (pin "B8") (pinfunction "B8_B8") (pintype "passive"))
      (node (ref "U4") (pin "15") (pinfunction "B-_15") (pintype "passive"))
    )
    (net (code "161") (name "/bus3_p") (class "Default")
      (node (ref "P3") (pin "B7") (pinfunction "B7_B7") (pintype "passive"))
      (node (ref "U4") (pin "14") (pinfunction "B+_14") (pintype "passive"))
    )
    (net (code "162") (name "/bus4_n") (class "Default")
      (node (ref "P3") (pin "B20") (pinfunction "B20_B20") (pintype "passive"))
      (node (ref "U8") (pin "1") (pinfunction "A-_1") (pintype "passive"))
    )
    (net (code "163") (name "/bus4_p") (class "Default")
      (node (ref "P3") (pin "B21") (pinfunction "B21_B21") (pintype "passive"))
      (node (ref "U8") (pin "2") (pinfunction "A+_2") (pintype "passive"))
    )
    (net (code "164") (name "/bus5_n") (class "Default")
      (node (ref "P3") (pin "B23") (pinfunction "B23_B23") (pintype "passive"))
      (node (ref "U8") (pin "7") (pinfunction "C-_7") (pintype "passive"))
    )
    (net (code "165") (name "/bus5_p") (class "Default")
      (node (ref "P3") (pin "B22") (pinfunction "B22_B22") (pintype "passive"))
      (node (ref "U8") (pin "6") (pinfunction "C+_6") (pintype "passive"))
    )
    (net (code "166") (name "/bus6_n") (class "Default")
      (node (ref "P3") (pin "B16") (pinfunction "B16_B16") (pintype "passive"))
      (node (ref "U8") (pin "9") (pinfunction "D-_9") (pintype "passive"))
    )
    (net (code "167") (name "/bus6_p") (class "Default")
      (node (ref "P3") (pin "B17") (pinfunction "B17_B17") (pintype "passive"))
      (node (ref "U8") (pin "10") (pinfunction "D+_10") (pintype "passive"))
    )
    (net (code "168") (name "/bus7_n") (class "Default")
      (node (ref "P3") (pin "B19") (pinfunction "B19_B19") (pintype "passive"))
      (node (ref "U8") (pin "15") (pinfunction "B-_15") (pintype "passive"))
    )
    (net (code "169") (name "/bus7_p") (class "Default")
      (node (ref "P3") (pin "B18") (pinfunction "B18_B18") (pintype "passive"))
      (node (ref "U8") (pin "14") (pinfunction "B+_14") (pintype "passive"))
    )
    (net (code "170") (name "/bus8_n") (class "Default")
      (node (ref "P3") (pin "B29") (pinfunction "B29_B29") (pintype "passive"))
      (node (ref "U12") (pin "1") (pinfunction "A-_1") (pintype "passive"))
    )
    (net (code "171") (name "/bus8_p") (class "Default")
      (node (ref "P3") (pin "B30") (pinfunction "B30_B30") (pintype "passive"))
      (node (ref "U12") (pin "2") (pinfunction "A+_2") (pintype "passive"))
    )
    (net (code "172") (name "/bus9_n") (class "Default")
      (node (ref "P3") (pin "B32") (pinfunction "B32_B32") (pintype "passive"))
      (node (ref "U12") (pin "7") (pinfunction "C-_7") (pintype "passive"))
    )
    (net (code "173") (name "/bus9_p") (class "Default")
      (node (ref "P3") (pin "B31") (pinfunction "B31_B31") (pintype "passive"))
      (node (ref "U12") (pin "6") (pinfunction "C+_6") (pintype "passive"))
    )
    (net (code "174") (name "/bus10_n") (class "Default")
      (node (ref "P3") (pin "B25") (pinfunction "B25_B25") (pintype "passive"))
      (node (ref "U12") (pin "9") (pinfunction "D-_9") (pintype "passive"))
    )
    (net (code "175") (name "/bus10_p") (class "Default")
      (node (ref "P3") (pin "B26") (pinfunction "B26_B26") (pintype "passive"))
      (node (ref "U12") (pin "10") (pinfunction "D+_10") (pintype "passive"))
    )
    (net (code "176") (name "/bus11_n") (class "Default")
      (node (ref "P3") (pin "B28") (pinfunction "B28_B28") (pintype "passive"))
      (node (ref "U12") (pin "15") (pinfunction "B-_15") (pintype "passive"))
    )
    (net (code "177") (name "/bus11_p") (class "Default")
      (node (ref "P3") (pin "B27") (pinfunction "B27_B27") (pintype "passive"))
      (node (ref "U12") (pin "14") (pinfunction "B+_14") (pintype "passive"))
    )
    (net (code "178") (name "/bus12_n") (class "Default")
      (node (ref "P3") (pin "B38") (pinfunction "B38_B38") (pintype "passive"))
      (node (ref "U5") (pin "1") (pinfunction "A-_1") (pintype "passive"))
    )
    (net (code "179") (name "/bus12_p") (class "Default")
      (node (ref "P3") (pin "B39") (pinfunction "B39_B39") (pintype "passive"))
      (node (ref "U5") (pin "2") (pinfunction "A+_2") (pintype "passive"))
    )
    (net (code "180") (name "/bus13_n") (class "Default")
      (node (ref "P3") (pin "B41") (pinfunction "B41_B41") (pintype "passive"))
      (node (ref "U5") (pin "7") (pinfunction "C-_7") (pintype "passive"))
    )
    (net (code "181") (name "/bus13_p") (class "Default")
      (node (ref "P3") (pin "B40") (pinfunction "B40_B40") (pintype "passive"))
      (node (ref "U5") (pin "6") (pinfunction "C+_6") (pintype "passive"))
    )
    (net (code "182") (name "/bus14_n") (class "Default")
      (node (ref "P3") (pin "B34") (pinfunction "B34_B34") (pintype "passive"))
      (node (ref "U5") (pin "9") (pinfunction "D-_9") (pintype "passive"))
    )
    (net (code "183") (name "/bus14_p") (class "Default")
      (node (ref "P3") (pin "B35") (pinfunction "B35_B35") (pintype "passive"))
      (node (ref "U5") (pin "10") (pinfunction "D+_10") (pintype "passive"))
    )
    (net (code "184") (name "/bus15_n") (class "Default")
      (node (ref "P3") (pin "B37") (pinfunction "B37_B37") (pintype "passive"))
      (node (ref "U5") (pin "15") (pinfunction "B-_15") (pintype "passive"))
    )
    (net (code "185") (name "/bus15_p") (class "Default")
      (node (ref "P3") (pin "B36") (pinfunction "B36_B36") (pintype "passive"))
      (node (ref "U5") (pin "14") (pinfunction "B+_14") (pintype "passive"))
    )
    (net (code "186") (name "/bus16_n") (class "Default")
      (node (ref "P3") (pin "A8") (pinfunction "A8_A8") (pintype "passive"))
      (node (ref "U9") (pin "1") (pinfunction "A-_1") (pintype "passive"))
    )
    (net (code "187") (name "/bus16_p") (class "Default")
      (node (ref "P3") (pin "A7") (pinfunction "A7_A7") (pintype "passive"))
      (node (ref "U9") (pin "2") (pinfunction "A+_2") (pintype "passive"))
    )
    (net (code "188") (name "/bus17_n") (class "Default")
      (node (ref "P3") (pin "A5") (pinfunction "A5_A5") (pintype "passive"))
      (node (ref "U9") (pin "7") (pinfunction "C-_7") (pintype "passive"))
    )
    (net (code "189") (name "/bus17_p") (class "Default")
      (node (ref "P3") (pin "A6") (pinfunction "A6_A6") (pintype "passive"))
      (node (ref "U9") (pin "6") (pinfunction "C+_6") (pintype "passive"))
    )
    (net (code "190") (name "/bus18_n") (class "Default")
      (node (ref "P3") (pin "A14") (pinfunction "A14_A14") (pintype "passive"))
      (node (ref "U9") (pin "9") (pinfunction "D-_9") (pintype "passive"))
    )
    (net (code "191") (name "/bus18_p") (class "Default")
      (node (ref "P3") (pin "A11") (pinfunction "A11_A11") (pintype "passive"))
      (node (ref "U9") (pin "10") (pinfunction "D+_10") (pintype "passive"))
    )
    (net (code "192") (name "/bus19_n") (class "Default")
      (node (ref "P3") (pin "A9") (pinfunction "A9_A9") (pintype "passive"))
      (node (ref "U9") (pin "15") (pinfunction "B-_15") (pintype "passive"))
    )
    (net (code "193") (name "/bus19_p") (class "Default")
      (node (ref "P3") (pin "A10") (pinfunction "A10_A10") (pintype "passive"))
      (node (ref "U9") (pin "14") (pinfunction "B+_14") (pintype "passive"))
    )
    (net (code "194") (name "/bus20_n") (class "Default")
      (node (ref "P3") (pin "A19") (pinfunction "A19_A19") (pintype "passive"))
      (node (ref "U20") (pin "1") (pinfunction "A-_1") (pintype "passive"))
    )
    (net (code "195") (name "/bus20_p") (class "Default")
      (node (ref "P3") (pin "A18") (pinfunction "A18_A18") (pintype "passive"))
      (node (ref "U20") (pin "2") (pinfunction "A+_2") (pintype "passive"))
    )
    (net (code "196") (name "/bus21_n") (class "Default")
      (node (ref "P3") (pin "A16") (pinfunction "A16_A16") (pintype "passive"))
      (node (ref "U20") (pin "7") (pinfunction "C-_7") (pintype "passive"))
    )
    (net (code "197") (name "/bus21_p") (class "Default")
      (node (ref "P3") (pin "A17") (pinfunction "A17_A17") (pintype "passive"))
      (node (ref "U20") (pin "6") (pinfunction "C+_6") (pintype "passive"))
    )
    (net (code "198") (name "/bus22_n") (class "Default")
      (node (ref "P3") (pin "A23") (pinfunction "A23_A23") (pintype "passive"))
      (node (ref "U20") (pin "9") (pinfunction "D-_9") (pintype "passive"))
    )
    (net (code "199") (name "/bus22_p") (class "Default")
      (node (ref "P3") (pin "A22") (pinfunction "A22_A22") (pintype "passive"))
      (node (ref "U20") (pin "10") (pinfunction "D+_10") (pintype "passive"))
    )
    (net (code "200") (name "/bus23_n") (class "Default")
      (node (ref "P3") (pin "A20") (pinfunction "A20_A20") (pintype "passive"))
      (node (ref "U20") (pin "15") (pinfunction "B-_15") (pintype "passive"))
    )
    (net (code "201") (name "/bus23_p") (class "Default")
      (node (ref "P3") (pin "A21") (pinfunction "A21_A21") (pintype "passive"))
      (node (ref "U20") (pin "14") (pinfunction "B+_14") (pintype "passive"))
    )
    (net (code "202") (name "/bus24_n") (class "Default")
      (node (ref "P3") (pin "A28") (pinfunction "A28_A28") (pintype "passive"))
      (node (ref "U6") (pin "1") (pinfunction "A-_1") (pintype "passive"))
    )
    (net (code "203") (name "/bus24_p") (class "Default")
      (node (ref "P3") (pin "A27") (pinfunction "A27_A27") (pintype "passive"))
      (node (ref "U6") (pin "2") (pinfunction "A+_2") (pintype "passive"))
    )
    (net (code "204") (name "/bus25_n") (class "Default")
      (node (ref "P3") (pin "A25") (pinfunction "A25_A25") (pintype "passive"))
      (node (ref "U6") (pin "7") (pinfunction "C-_7") (pintype "passive"))
    )
    (net (code "205") (name "/bus25_p") (class "Default")
      (node (ref "P3") (pin "A26") (pinfunction "A26_A26") (pintype "passive"))
      (node (ref "U6") (pin "6") (pinfunction "C+_6") (pintype "passive"))
    )
    (net (code "206") (name "/bus26_n") (class "Default")
      (node (ref "P3") (pin "A32") (pinfunction "A32_A32") (pintype "passive"))
      (node (ref "U6") (pin "9") (pinfunction "D-_9") (pintype "passive"))
    )
    (net (code "207") (name "/bus26_p") (class "Default")
      (node (ref "P3") (pin "A31") (pinfunction "A31_A31") (pintype "passive"))
      (node (ref "U6") (pin "10") (pinfunction "D+_10") (pintype "passive"))
    )
    (net (code "208") (name "/bus27_n") (class "Default")
      (node (ref "P3") (pin "A29") (pinfunction "A29_A29") (pintype "passive"))
      (node (ref "U6") (pin "15") (pinfunction "B-_15") (pintype "passive"))
    )
    (net (code "209") (name "/bus27_p") (class "Default")
      (node (ref "P3") (pin "A30") (pinfunction "A30_A30") (pintype "passive"))
      (node (ref "U6") (pin "14") (pinfunction "B+_14") (pintype "passive"))
    )
    (net (code "210") (name "/bus28_n") (class "Default")
      (node (ref "P3") (pin "A37") (pinfunction "A37_A37") (pintype "passive"))
      (node (ref "U10") (pin "1") (pinfunction "A-_1") (pintype "passive"))
    )
    (net (code "211") (name "/bus28_p") (class "Default")
      (node (ref "P3") (pin "A36") (pinfunction "A36_A36") (pintype "passive"))
      (node (ref "U10") (pin "2") (pinfunction "A+_2") (pintype "passive"))
    )
    (net (code "212") (name "/bus29_n") (class "Default")
      (node (ref "P3") (pin "A34") (pinfunction "A34_A34") (pintype "passive"))
      (node (ref "U10") (pin "7") (pinfunction "C-_7") (pintype "passive"))
    )
    (net (code "213") (name "/bus29_p") (class "Default")
      (node (ref "P3") (pin "A35") (pinfunction "A35_A35") (pintype "passive"))
      (node (ref "U10") (pin "6") (pinfunction "C+_6") (pintype "passive"))
    )
    (net (code "214") (name "/bus30_n") (class "Default")
      (node (ref "P3") (pin "A41") (pinfunction "A41_A41") (pintype "passive"))
      (node (ref "U10") (pin "9") (pinfunction "D-_9") (pintype "passive"))
    )
    (net (code "215") (name "/bus30_p") (class "Default")
      (node (ref "P3") (pin "A40") (pinfunction "A40_A40") (pintype "passive"))
      (node (ref "U10") (pin "10") (pinfunction "D+_10") (pintype "passive"))
    )
    (net (code "216") (name "/bus31_n") (class "Default")
      (node (ref "P3") (pin "A38") (pinfunction "A38_A38") (pintype "passive"))
      (node (ref "U10") (pin "15") (pinfunction "B-_15") (pintype "passive"))
    )
    (net (code "217") (name "/bus31_p") (class "Default")
      (node (ref "P3") (pin "A39") (pinfunction "A39_A39") (pintype "passive"))
      (node (ref "U10") (pin "14") (pinfunction "B+_14") (pintype "passive"))
    )
    (net (code "218") (name "/bus32_n") (class "Default")
      (node (ref "P3") (pin "B48") (pinfunction "B48_B48") (pintype "passive"))
      (node (ref "U7") (pin "3") (pinfunction "DO1-_3") (pintype "passive"))
    )
    (net (code "219") (name "/bus32_p") (class "Default")
      (node (ref "P3") (pin "B47") (pinfunction "B47_B47") (pintype "passive"))
      (node (ref "U7") (pin "2") (pinfunction "DO1+_2") (pintype "passive"))
    )
    (net (code "220") (name "/bus33_n") (class "Default")
      (node (ref "P3") (pin "B49") (pinfunction "B49_B49") (pintype "passive"))
      (node (ref "U7") (pin "5") (pinfunction "DO2-_5") (pintype "passive"))
    )
    (net (code "221") (name "/bus33_p") (class "Default")
      (node (ref "P3") (pin "B50") (pinfunction "B50_B50") (pintype "passive"))
      (node (ref "U7") (pin "6") (pinfunction "DO2+_6") (pintype "passive"))
    )
    (net (code "222") (name "/bus34_n") (class "Default")
      (node (ref "P3") (pin "B44") (pinfunction "B44_B44") (pintype "passive"))
      (node (ref "U7") (pin "11") (pinfunction "DO3-_11") (pintype "passive"))
    )
    (net (code "223") (name "/bus34_p") (class "Default")
      (node (ref "P3") (pin "B43") (pinfunction "B43_B43") (pintype "passive"))
      (node (ref "U7") (pin "10") (pinfunction "DO3+_10") (pintype "passive"))
    )
    (net (code "224") (name "/bus35_n") (class "Default")
      (node (ref "P3") (pin "B45") (pinfunction "B45_B45") (pintype "passive"))
      (node (ref "U7") (pin "13") (pinfunction "DO4-_13") (pintype "passive"))
    )
    (net (code "225") (name "/bus35_p") (class "Default")
      (node (ref "P3") (pin "B46") (pinfunction "B46_B46") (pintype "passive"))
      (node (ref "U7") (pin "14") (pinfunction "DO4+_14") (pintype "passive"))
    )
    (net (code "226") (name "/bus36_n") (class "Default")
      (node (ref "P3") (pin "A45") (pinfunction "A45_A45") (pintype "passive"))
      (node (ref "U11") (pin "3") (pinfunction "DO1-_3") (pintype "passive"))
    )
    (net (code "227") (name "/bus36_p") (class "Default")
      (node (ref "P3") (pin "A46") (pinfunction "A46_A46") (pintype "passive"))
      (node (ref "U11") (pin "2") (pinfunction "DO1+_2") (pintype "passive"))
    )
    (net (code "228") (name "/bus37_n") (class "Default")
      (node (ref "P3") (pin "A44") (pinfunction "A44_A44") (pintype "passive"))
      (node (ref "U11") (pin "5") (pinfunction "DO2-_5") (pintype "passive"))
    )
    (net (code "229") (name "/bus37_p") (class "Default")
      (node (ref "P3") (pin "A43") (pinfunction "A43_A43") (pintype "passive"))
      (node (ref "U11") (pin "6") (pinfunction "DO2+_6") (pintype "passive"))
    )
    (net (code "230") (name "/bus38_n") (class "Default")
      (node (ref "P3") (pin "A49") (pinfunction "A49_A49") (pintype "passive"))
      (node (ref "U11") (pin "11") (pinfunction "DO3-_11") (pintype "passive"))
    )
    (net (code "231") (name "/bus38_p") (class "Default")
      (node (ref "P3") (pin "A50") (pinfunction "A50_A50") (pintype "passive"))
      (node (ref "U11") (pin "10") (pinfunction "DO3+_10") (pintype "passive"))
    )
    (net (code "232") (name "/bus39_n") (class "Default")
      (node (ref "P3") (pin "A48") (pinfunction "A48_A48") (pintype "passive"))
      (node (ref "U11") (pin "13") (pinfunction "DO4-_13") (pintype "passive"))
    )
    (net (code "233") (name "/bus39_p") (class "Default")
      (node (ref "P3") (pin "A47") (pinfunction "A47_A47") (pintype "passive"))
      (node (ref "U11") (pin "14") (pinfunction "DO4+_14") (pintype "passive"))
    )
    (net (code "234") (name "/gain_control") (class "Default")
      (node (ref "C76") (pin "1") (pinfunction "1_1") (pintype "passive"))
      (node (ref "P8") (pin "2") (pinfunction "2_2") (pintype "passive"))
      (node (ref "U22") (pin "24") (pinfunction "GAIN_24") (pintype "input"))
    )
    (net (code "235") (name "1.8V_ana") (class "Default")
      (node (ref "C29") (pin "1") (pinfunction "1_1") (pintype "passive"))
      (node (ref "C71") (pin "1") (pinfunction "1_1") (pintype "passive"))
      (node (ref "U3") (pin "32") (pinfunction "AVDD_(1.8V)_32") (pintype "passive"))
      (node (ref "U3") (pin "56") (pinfunction "AVDD_(1.8V)_56") (pintype "passive"))
      (node (ref "U3") (pin "57") (pinfunction "AVDD_(1.8V)_57") (pintype "passive"))
    )
    (net (code "236") (name "1.8V_dig") (class "Default")
      (node (ref "C26") (pin "1") (pinfunction "1_1") (pintype "passive"))
      (node (ref "U3") (pin "23") (pinfunction "DVDD_(1.8V)_23") (pintype "passive"))
      (node (ref "U3") (pin "6") (pinfunction "DVDD_(1.8V)_6") (pintype "passive"))
      (node (ref "U3") (pin "73") (pinfunction "DVDD_(1.8V)_73") (pintype "passive"))
    )
    (net (code "237") (name "3.3V_ana") (class "Default")
      (node (ref "C27") (pin "1") (pinfunction "1_1") (pintype "passive"))
      (node (ref "C28") (pin "1") (pinfunction "1_1") (pintype "passive"))
      (node (ref "C87") (pin "2") (pinfunction "2_2") (pintype "passive"))
      (node (ref "U21") (pin "24") (pinfunction "AVDD_24") (pintype "power_in"))
      (node (ref "U3") (pin "34") (pinfunction "AVDD_(3.3V)_34") (pintype "passive"))
      (node (ref "U3") (pin "36") (pinfunction "AVDD_(3.3V)_36") (pintype "passive"))
      (node (ref "U3") (pin "39") (pinfunction "AVDD_(3.3V)_39") (pintype "passive"))
      (node (ref "U3") (pin "40") (pinfunction "AVDD_(3.3V)_40") (pintype "passive"))
      (node (ref "U3") (pin "43") (pinfunction "AVDD_(3.3V)_43") (pintype "passive"))
      (node (ref "U3") (pin "47") (pinfunction "AVDD_(3.3V)_47") (pintype "passive"))
      (node (ref "U3") (pin "50") (pinfunction "AVDD_(3.3V)_50") (pintype "passive"))
      (node (ref "U3") (pin "52") (pinfunction "AVDD_(3.3V)_52") (pintype "passive"))
      (node (ref "U3") (pin "53") (pinfunction "AVDD_(3.3V)_53") (pintype "passive"))
      (node (ref "U3") (pin "60") (pinfunction "AVDD_(3.3V)_60") (pintype "passive"))
    )
    (net (code "238") (name "3.3V_dig") (class "Default")
      (node (ref "C25") (pin "1") (pinfunction "1_1") (pintype "passive"))
      (node (ref "C30") (pin "1") (pinfunction "1_1") (pintype "passive"))
      (node (ref "C31") (pin "1") (pinfunction "1_1") (pintype "passive"))
      (node (ref "C32") (pin "1") (pinfunction "1_1") (pintype "passive"))
      (node (ref "C33") (pin "1") (pinfunction "1_1") (pintype "passive"))
      (node (ref "C34") (pin "1") (pinfunction "1_1") (pintype "passive"))
      (node (ref "C35") (pin "1") (pinfunction "1_1") (pintype "passive"))
      (node (ref "C36") (pin "1") (pinfunction "1_1") (pintype "passive"))
      (node (ref "C37") (pin "1") (pinfunction "1_1") (pintype "passive"))
      (node (ref "C67") (pin "1") (pinfunction "1_1") (pintype "passive"))
      (node (ref "C68") (pin "1") (pinfunction "1_1") (pintype "passive"))
      (node (ref "C69") (pin "1") (pinfunction "1_1") (pintype "passive"))
      (node (ref "C88") (pin "1") (pinfunction "1_1") (pintype "passive"))
      (node (ref "D10") (pin "1") (pinfunction "A_1") (pintype "passive"))
      (node (ref "D11") (pin "1") (pinfunction "A_1") (pintype "passive"))
      (node (ref "D12") (pin "1") (pinfunction "A_1") (pintype "passive"))
      (node (ref "D5") (pin "1") (pinfunction "A_1") (pintype "passive"))
      (node (ref "D6") (pin "1") (pinfunction "A_1") (pintype "passive"))
      (node (ref "D7") (pin "1") (pinfunction "A_1") (pintype "passive"))
      (node (ref "D8") (pin "1") (pinfunction "A_1") (pintype "passive"))
      (node (ref "D9") (pin "1") (pinfunction "A_1") (pintype "passive"))
      (node (ref "P4") (pin "1") (pinfunction "1_1") (pintype "passive"))
      (node (ref "P4") (pin "3") (pinfunction "3_3") (pintype "passive"))
      (node (ref "P4") (pin "5") (pinfunction "5_5") (pintype "passive"))
      (node (ref "P4") (pin "7") (pinfunction "7_7") (pintype "passive"))
      (node (ref "U10") (pin "12") (pinfunction "ENBD_12") (pintype "passive"))
      (node (ref "U10") (pin "16") (pinfunction "Vcc_16") (pintype "passive"))
      (node (ref "U10") (pin "4") (pinfunction "EAC_4") (pintype "passive"))
      (node (ref "U11") (pin "12") (pinfunction "EN#_12") (pintype "passive"))
      (node (ref "U11") (pin "16") (pinfunction "Vcc_16") (pintype "passive"))
      (node (ref "U12") (pin "12") (pinfunction "ENBD_12") (pintype "passive"))
      (node (ref "U12") (pin "16") (pinfunction "Vcc_16") (pintype "passive"))
      (node (ref "U12") (pin "4") (pinfunction "EAC_4") (pintype "passive"))
      (node (ref "U20") (pin "12") (pinfunction "ENBD_12") (pintype "passive"))
      (node (ref "U20") (pin "16") (pinfunction "Vcc_16") (pintype "passive"))
      (node (ref "U20") (pin "4") (pinfunction "EAC_4") (pintype "passive"))
      (node (ref "U21") (pin "27") (pinfunction "DVDD_27") (pintype "power_in"))
      (node (ref "U23") (pin "16") (pinfunction "VDD_16") (pintype "passive"))
      (node (ref "U3") (pin "16") (pinfunction "DVDD_I/O_(3.3V)_16") (pintype "passive"))
      (node (ref "U3") (pin "83") (pinfunction "DVDD_I/O_(3.3V)_83") (pintype "passive"))
      (node (ref "U4") (pin "12") (pinfunction "ENBD_12") (pintype "passive"))
      (node (ref "U4") (pin "16") (pinfunction "Vcc_16") (pintype "passive"))
      (node (ref "U4") (pin "4") (pinfunction "EAC_4") (pintype "passive"))
      (node (ref "U5") (pin "12") (pinfunction "ENBD_12") (pintype "passive"))
      (node (ref "U5") (pin "16") (pinfunction "Vcc_16") (pintype "passive"))
      (node (ref "U5") (pin "4") (pinfunction "EAC_4") (pintype "passive"))
      (node (ref "U6") (pin "12") (pinfunction "ENBD_12") (pintype "passive"))
      (node (ref "U6") (pin "16") (pinfunction "Vcc_16") (pintype "passive"))
      (node (ref "U6") (pin "4") (pinfunction "EAC_4") (pintype "passive"))
      (node (ref "U7") (pin "12") (pinfunction "EN#_12") (pintype "passive"))
      (node (ref "U7") (pin "16") (pinfunction "Vcc_16") (pintype "passive"))
      (node (ref "U8") (pin "12") (pinfunction "ENBD_12") (pintype "passive"))
      (node (ref "U8") (pin "16") (pinfunction "Vcc_16") (pintype "passive"))
      (node (ref "U8") (pin "4") (pinfunction "EAC_4") (pintype "passive"))
      (node (ref "U9") (pin "12") (pinfunction "ENBD_12") (pintype "passive"))
      (node (ref "U9") (pin "16") (pinfunction "Vcc_16") (pintype "passive"))
      (node (ref "U9") (pin "4") (pinfunction "EAC_4") (pintype "passive"))
    )
    (net (code "239") (name "5V") (class "Default")
      (node (ref "C70") (pin "2") (pinfunction "2_2") (pintype "passive"))
      (node (ref "C72") (pin "1") (pinfunction "1_1") (pintype "passive"))
      (node (ref "C73") (pin "1") (pinfunction "1_1") (pintype "passive"))
      (node (ref "C75") (pin "1") (pinfunction "1_1") (pintype "passive"))
      (node (ref "R21") (pin "2") (pinfunction "2_2") (pintype "passive"))
      (node (ref "T3") (pin "2") (pinfunction "SecCT_2") (pintype "passive"))
      (node (ref "U22") (pin "1") (pinfunction "VPS1_1") (pintype "power_in"))
      (node (ref "U22") (pin "13") (pinfunction "VPS2_13") (pintype "power_in"))
      (node (ref "U22") (pin "18") (pinfunction "VPS2_18") (pintype "power_in"))
      (node (ref "U22") (pin "19") (pinfunction "VPS2_19") (pintype "power_in"))
      (node (ref "U22") (pin "20") (pinfunction "VPS2_20") (pintype "power_in"))
      (node (ref "U22") (pin "21") (pinfunction "VPS2_21") (pintype "power_in"))
      (node (ref "U22") (pin "22") (pinfunction "VPS2_22") (pintype "power_in"))
      (node (ref "U22") (pin "23") (pinfunction "ENBL_23") (pintype "input"))
      (node (ref "U22") (pin "6") (pinfunction "VPS1_6") (pintype "power_in"))
    )
    (net (code "240") (name "5V_ANA_BUS") (class "Default")
      (node (ref "P3") (pin "A3") (pinfunction "A3_A3") (pintype "passive"))
      (node (ref "P3") (pin "B3") (pinfunction "B3_B3") (pintype "passive"))
    )
    (net (code "241") (name "5V_DIG_BUS") (class "Default")
      (node (ref "P3") (pin "A62") (pinfunction "A62_A62") (pintype "passive"))
      (node (ref "P3") (pin "B62") (pinfunction "B62_B62") (pintype "passive"))
    )
    (net (code "242") (name "8V_BUS") (class "Default")
      (node (ref "P3") (pin "A1") (pinfunction "A1_A1") (pintype "passive"))
      (node (ref "P3") (pin "B1") (pinfunction "B1_B1") (pintype "passive"))
    )
    (net (code "243") (name "AGND") (class "Default")
      (node (ref "C23") (pin "2") (pinfunction "2_2") (pintype "passive"))
      (node (ref "C24") (pin "1") (pinfunction "1_1") (pintype "passive"))
      (node (ref "C25") (pin "2") (pinfunction "2_2") (pintype "passive"))
      (node (ref "C26") (pin "2") (pinfunction "2_2") (pintype "passive"))
      (node (ref "C27") (pin "2") (pinfunction "2_2") (pintype "passive"))
      (node (ref "C28") (pin "2") (pinfunction "2_2") (pintype "passive"))
      (node (ref "C29") (pin "2") (pinfunction "2_2") (pintype "passive"))
      (node (ref "C30") (pin "2") (pinfunction "2_2") (pintype "passive"))
      (node (ref "C31") (pin "2") (pinfunction "2_2") (pintype "passive"))
      (node (ref "C32") (pin "2") (pinfunction "2_2") (pintype "passive"))
      (node (ref "C33") (pin "2") (pinfunction "2_2") (pintype "passive"))
      (node (ref "C34") (pin "2") (pinfunction "2_2") (pintype "passive"))
      (node (ref "C35") (pin "2") (pinfunction "2_2") (pintype "passive"))
      (node (ref "C36") (pin "2") (pinfunction "2_2") (pintype "passive"))
      (node (ref "C37") (pin "2") (pinfunction "2_2") (pintype "passive"))
      (node (ref "C67") (pin "2") (pinfunction "2_2") (pintype "passive"))
      (node (ref "C68") (pin "2") (pinfunction "2_2") (pintype "passive"))
      (node (ref "C69") (pin "2") (pinfunction "2_2") (pintype "passive"))
      (node (ref "C70") (pin "1") (pinfunction "1_1") (pintype "passive"))
      (node (ref "C71") (pin "2") (pinfunction "2_2") (pintype "passive"))
      (node (ref "C72") (pin "2") (pinfunction "2_2") (pintype "passive"))
      (node (ref "C73") (pin "2") (pinfunction "2_2") (pintype "passive"))
      (node (ref "C74") (pin "1") (pinfunction "1_1") (pintype "passive"))
      (node (ref "C75") (pin "2") (pinfunction "2_2") (pintype "passive"))
      (node (ref "C76") (pin "2") (pinfunction "2_2") (pintype "passive"))
      (node (ref "C77") (pin "1") (pinfunction "1_1") (pintype "passive"))
      (node (ref "C78") (pin "1") (pinfunction "1_1") (pintype "passive"))
      (node (ref "C87") (pin "1") (pinfunction "1_1") (pintype "passive"))
      (node (ref "C88") (pin "2") (pinfunction "2_2") (pintype "passive"))
      (node (ref "J2") (pin "1") (pinfunction "1_1") (pintype "passive"))
      (node (ref "P3") (pin "A15") (pinfunction "A15_A15") (pintype "passive"))
      (node (ref "P3") (pin "A2") (pinfunction "A2_A2") (pintype "passive"))
      (node (ref "P3") (pin "A24") (pinfunction "A24_A24") (pintype "passive"))
      (node (ref "P3") (pin "A33") (pinfunction "A33_A33") (pintype "passive"))
      (node (ref "P3") (pin "A4") (pinfunction "A4_A4") (pintype "passive"))
      (node (ref "P3") (pin "A42") (pinfunction "A42_A42") (pintype "passive"))
      (node (ref "P3") (pin "A57") (pinfunction "A57_A57") (pintype "passive"))
      (node (ref "P3") (pin "A58") (pinfunction "A58_A58") (pintype "passive"))
      (node (ref "P3") (pin "A59") (pinfunction "A59_A59") (pintype "passive"))
      (node (ref "P3") (pin "A60") (pinfunction "A60_A60") (pintype "passive"))
      (node (ref "P3") (pin "A61") (pinfunction "A61_A61") (pintype "passive"))
      (node (ref "P3") (pin "B15") (pinfunction "B15_B15") (pintype "passive"))
      (node (ref "P3") (pin "B2") (pinfunction "B2_B2") (pintype "passive"))
      (node (ref "P3") (pin "B24") (pinfunction "B24_B24") (pintype "passive"))
      (node (ref "P3") (pin "B33") (pinfunction "B33_B33") (pintype "passive"))
      (node (ref "P3") (pin "B4") (pinfunction "B4_B4") (pintype "passive"))
      (node (ref "P3") (pin "B42") (pinfunction "B42_B42") (pintype "passive"))
      (node (ref "P3") (pin "B57") (pinfunction "B57_B57") (pintype "passive"))
      (node (ref "P3") (pin "B58") (pinfunction "B58_B58") (pintype "passive"))
      (node (ref "P3") (pin "B59") (pinfunction "B59_B59") (pintype "passive"))
      (node (ref "P3") (pin "B60") (pinfunction "B60_B60") (pintype "passive"))
      (node (ref "P3") (pin "B61") (pinfunction "B61_B61") (pintype "passive"))
      (node (ref "P5") (pin "1") (pintype "passive"))
      (node (ref "P5") (pin "10") (pinfunction "A18_10") (pintype "passive"))
      (node (ref "P5") (pin "11") (pinfunction "A26_11") (pintype "passive"))
      (node (ref "P5") (pin "12") (pinfunction "A25_12") (pintype "passive"))
      (node (ref "P5") (pin "13") (pinfunction "A23_13") (pintype "passive"))
      (node (ref "P5") (pin "14") (pinfunction "A24_14") (pintype "passive"))
      (node (ref "P5") (pin "15") (pinfunction "A22_15") (pintype "passive"))
      (node (ref "P5") (pin "16") (pinfunction "A19_16") (pintype "passive"))
      (node (ref "P5") (pin "17") (pinfunction "A20_17") (pintype "passive"))
      (node (ref "P5") (pin "18") (pinfunction "A21_18") (pintype "passive"))
      (node (ref "P5") (pin "19") (pinfunction "A8_19") (pintype "passive"))
      (node (ref "P5") (pin "2") (pinfunction "A10_2") (pintype "passive"))
      (node (ref "P5") (pin "20") (pinfunction "A7_20") (pintype "passive"))
      (node (ref "P5") (pin "21") (pinfunction "A6_21") (pintype "passive"))
      (node (ref "P5") (pin "22") (pinfunction "A5_22") (pintype "passive"))
      (node (ref "P5") (pin "23") (pinfunction "A4_23") (pintype "passive"))
      (node (ref "P5") (pin "24") (pinfunction "A3_24") (pintype "passive"))
      (node (ref "P5") (pin "3") (pinfunction "A11_3") (pintype "passive"))
      (node (ref "P5") (pin "4") (pinfunction "A12_4") (pintype "passive"))
      (node (ref "P5") (pin "5") (pinfunction "A13_5") (pintype "passive"))
      (node (ref "P5") (pin "6") (pinfunction "A14_6") (pintype "passive"))
      (node (ref "P5") (pin "7") (pinfunction "A15_7") (pintype "passive"))
      (node (ref "P5") (pin "8") (pinfunction "A16_8") (pintype "passive"))
      (node (ref "P5") (pin "9") (pinfunction "A17_9") (pintype "passive"))
      (node (ref "P7") (pin "1") (pinfunction "X_1") (pintype "passive"))
      (node (ref "P9") (pin "1") (pinfunction "1_1") (pintype "passive"))
      (node (ref "P9") (pin "2") (pinfunction "2_2") (pintype "passive"))
      (node (ref "P9") (pin "3") (pinfunction "3_3") (pintype "passive"))
      (node (ref "P9") (pin "4") (pinfunction "4_4") (pintype "passive"))
      (node (ref "R12") (pin "2") (pinfunction "2_2") (pintype "passive"))
      (node (ref "R13") (pin "1") (pinfunction "1_1") (pintype "passive"))
      (node (ref "R14") (pin "2") (pinfunction "2_2") (pintype "passive"))
      (node (ref "R15") (pin "1") (pinfunction "1_1") (pintype "passive"))
      (node (ref "R16") (pin "2") (pinfunction "2_2") (pintype "passive"))
      (node (ref "R17") (pin "2") (pinfunction "2_2") (pintype "passive"))
      (node (ref "R18") (pin "2") (pinfunction "2_2") (pintype "passive"))
      (node (ref "R22") (pin "1") (pinfunction "1_1") (pintype "passive"))
      (node (ref "R8") (pin "2") (pinfunction "2_2") (pintype "passive"))
      (node (ref "R9") (pin "1") (pinfunction "1_1") (pintype "passive"))
      (node (ref "T3") (pin "4") (pinfunction "Pri-_4") (pintype "passive"))
      (node (ref "U10") (pin "8") (pinfunction "GND_8") (pintype "passive"))
      (node (ref "U11") (pin "8") (pinfunction "GND_8") (pintype "passive"))
      (node (ref "U12") (pin "8") (pinfunction "GND_8") (pintype "passive"))
      (node (ref "U20") (pin "8") (pinfunction "GND_8") (pintype "passive"))
      (node (ref "U21") (pin "16") (pinfunction "RefLo_16") (pintype "power_in"))
      (node (ref "U21") (pin "20") (pinfunction "ACOM_20") (pintype "power_in"))
      (node (ref "U21") (pin "25") (pinfunction "Mode_25") (pintype "power_in"))
      (node (ref "U21") (pin "26") (pinfunction "DCOM_26") (pintype "power_in"))
      (node (ref "U22") (pin "10") (pinfunction "COM2_10") (pintype "power_in"))
      (node (ref "U22") (pin "11") (pinfunction "COM2_11") (pintype "power_in"))
      (node (ref "U22") (pin "12") (pinfunction "COM2_12") (pintype "power_in"))
      (node (ref "U22") (pin "14") (pinfunction "COM2_14") (pintype "power_in"))
      (node (ref "U22") (pin "17") (pinfunction "COM2_17") (pintype "power_in"))
      (node (ref "U22") (pin "2") (pinfunction "COM1_2") (pintype "power_in"))
      (node (ref "U22") (pin "25") (pinfunction "Thermal_Pad_25") (pintype "power_in"))
      (node (ref "U22") (pin "5") (pinfunction "COM1_5") (pintype "power_in"))
      (node (ref "U23") (pin "1") (pinfunction "GND_1") (pintype "passive"))
      (node (ref "U26") (pin "2") (pinfunction "GND_2") (pintype "power_in"))
      (node (ref "U26") (pin "3") (pinfunction "GND_3") (pintype "power_in"))
      (node (ref "U26") (pin "4") (pinfunction "GND_4") (pintype "power_in"))
      (node (ref "U26") (pin "5") (pinfunction "GND_5") (pintype "power_in"))
      (node (ref "U26") (pin "6") (pinfunction "GND_6") (pintype "power_in"))
      (node (ref "U26") (pin "7") (pinfunction "GND_7") (pintype "power_in"))
      (node (ref "U3") (pin "17") (pinfunction "DGND_17") (pintype "passive"))
      (node (ref "U3") (pin "24") (pinfunction "DGND_24") (pintype "passive"))
      (node (ref "U3") (pin "33") (pinfunction "AGND_33") (pintype "passive"))
      (node (ref "U3") (pin "35") (pinfunction "AGND_35") (pintype "passive"))
      (node (ref "U3") (pin "37") (pinfunction "AGND_37") (pintype "passive"))
      (node (ref "U3") (pin "38") (pinfunction "AGND_38") (pintype "passive"))
      (node (ref "U3") (pin "44") (pinfunction "AGND_44") (pintype "passive"))
      (node (ref "U3") (pin "46") (pinfunction "AGND_46") (pintype "passive"))
      (node (ref "U3") (pin "49") (pinfunction "AGND_49") (pintype "passive"))
      (node (ref "U3") (pin "51") (pinfunction "AGND_51") (pintype "passive"))
      (node (ref "U3") (pin "61") (pinfunction "SYNC_OUT_61") (pintype "passive"))
      (node (ref "U3") (pin "62") (pinfunction "SYNC_IN_62") (pintype "passive"))
      (node (ref "U3") (pin "67") (pinfunction "EXT_PWR_DWN_67") (pintype "passive"))
      (node (ref "U3") (pin "7") (pinfunction "DGND_7") (pintype "passive"))
      (node (ref "U3") (pin "74") (pinfunction "DGND_74") (pintype "passive"))
      (node (ref "U3") (pin "84") (pinfunction "DGND_84") (pintype "passive"))
      (node (ref "U3") (pin "89") (pinfunction "EP_89") (pintype "passive"))
      (node (ref "U4") (pin "8") (pinfunction "GND_8") (pintype "passive"))
      (node (ref "U5") (pin "8") (pinfunction "GND_8") (pintype "passive"))
      (node (ref "U6") (pin "8") (pinfunction "GND_8") (pintype "passive"))
      (node (ref "U7") (pin "8") (pinfunction "GND_8") (pintype "passive"))
      (node (ref "U8") (pin "8") (pinfunction "GND_8") (pintype "passive"))
      (node (ref "U9") (pin "8") (pinfunction "GND_8") (pintype "passive"))
    )
    (net (code "244") (name "Net-(D5-K)") (class "Default")
      (node (ref "D5") (pin "2") (pinfunction "K_2") (pintype "passive"))
      (node (ref "U23") (pin "11") (pinfunction "OUT6_11") (pintype "passive"))
    )
    (net (code "245") (name "Net-(D6-K)") (class "Default")
      (node (ref "D6") (pin "2") (pinfunction "K_2") (pintype "passive"))
      (node (ref "U23") (pin "8") (pinfunction "OUT3_8") (pintype "passive"))
    )
    (net (code "246") (name "Net-(D7-K)") (class "Default")
      (node (ref "D7") (pin "2") (pinfunction "K_2") (pintype "passive"))
      (node (ref "U23") (pin "10") (pinfunction "OUT5_10") (pintype "passive"))
    )
    (net (code "247") (name "Net-(D8-K)") (class "Default")
      (node (ref "D8") (pin "2") (pinfunction "K_2") (pintype "passive"))
      (node (ref "U23") (pin "9") (pinfunction "OUT4_9") (pintype "passive"))
    )
    (net (code "248") (name "Net-(D9-K)") (class "Default")
      (node (ref "D9") (pin "2") (pinfunction "K_2") (pintype "passive"))
      (node (ref "U23") (pin "5") (pinfunction "OUT0_5") (pintype "passive"))
    )
    (net (code "249") (name "Net-(D10-K)") (class "Default")
      (node (ref "D10") (pin "2") (pinfunction "K_2") (pintype "passive"))
      (node (ref "U23") (pin "6") (pinfunction "OUT1_6") (pintype "passive"))
    )
    (net (code "250") (name "Net-(D11-K)") (class "Default")
      (node (ref "D11") (pin "2") (pinfunction "K_2") (pintype "passive"))
      (node (ref "U23") (pin "12") (pinfunction "OUT7_12") (pintype "passive"))
    )
    (net (code "251") (name "Net-(D12-K)") (class "Default")
      (node (ref "D12") (pin "2") (pinfunction "K_2") (pintype "passive"))
      (node (ref "U23") (pin "7") (pinfunction "OUT2_7") (pintype "passive"))
    )
    (net (code "252") (name "Net-(P6-X)") (class "Default")
      (node (ref "C84") (pin "2") (pinfunction "2_2") (pintype "passive"))
      (node (ref "P6") (pin "1") (pinfunction "X_1") (pintype "passive"))
      (node (ref "R20") (pin "1") (pinfunction "1_1") (pintype "passive"))
    )
    (net (code "253") (name "Net-(P6-Y)") (class "Default")
      (node (ref "C83") (pin "2") (pinfunction "2_2") (pintype "passive"))
      (node (ref "P6") (pin "2") (pinfunction "Y_2") (pintype "passive"))
      (node (ref "R20") (pin "2") (pinfunction "2_2") (pintype "passive"))
    )
    (net (code "254") (name "Net-(P7-Y)") (class "Default")
      (node (ref "P7") (pin "2") (pinfunction "Y_2") (pintype "passive"))
      (node (ref "U26") (pin "8") (pinfunction "Output_8") (pintype "output"))
    )
    (net (code "255") (name "Net-(T3-Pri+)") (class "Default")
      (node (ref "T3") (pin "6") (pinfunction "Pri+_6") (pintype "passive"))
      (node (ref "U26") (pin "1") (pinfunction "Input_1") (pintype "input"))
    )
    (net (code "256") (name "Net-(T3-Sec+)") (class "Default")
      (node (ref "T3") (pin "3") (pinfunction "Sec+_3") (pintype "passive"))
      (node (ref "U22") (pin "15") (pinfunction "OPLO_15") (pintype "output"))
    )
    (net (code "257") (name "Net-(T3-Sec-)") (class "Default")
      (node (ref "T3") (pin "1") (pinfunction "Sec-_1") (pintype "passive"))
      (node (ref "U22") (pin "16") (pinfunction "OPHI_16") (pintype "output"))
    )
    (net (code "258") (name "Net-(U3-DAC_BP)") (class "Default")
      (node (ref "C24") (pin "2") (pinfunction "2_2") (pintype "passive"))
      (node (ref "U3") (pin "45") (pinfunction "DAC_BP_45") (pintype "passive"))
    )
    (net (code "259") (name "Net-(U3-DAC_RSET)") (class "Default")
      (node (ref "R8") (pin "1") (pinfunction "1_1") (pintype "passive"))
      (node (ref "U3") (pin "48") (pinfunction "DAC_RSET_48") (pintype "passive"))
    )
    (net (code "260") (name "Net-(U3-LOOP_FILTER)") (class "Default")
      (node (ref "C22") (pin "1") (pinfunction "1_1") (pintype "passive"))
      (node (ref "U3") (pin "58") (pinfunction "LOOP_FILTER_58") (pintype "passive"))
    )
    (net (code "261") (name "Net-(U3-REF)") (class "Default")
      (node (ref "C22") (pin "2") (pinfunction "2_2") (pintype "passive"))
      (node (ref "C23") (pin "1") (pinfunction "1_1") (pintype "passive"))
      (node (ref "U3") (pin "59") (pinfunction "REF_59") (pintype "passive"))
    )
    (net (code "262") (name "Net-(U21-FS_Adj)") (class "Default")
      (node (ref "R13") (pin "2") (pinfunction "2_2") (pintype "passive"))
      (node (ref "U21") (pin "18") (pinfunction "FS_Adj_18") (pintype "power_in"))
    )
    (net (code "263") (name "Net-(U21-IOUTB)") (class "Default")
      (node (ref "R12") (pin "1") (pinfunction "1_1") (pintype "passive"))
      (node (ref "U21") (pin "21") (pinfunction "IOUTB_21") (pintype "power_in"))
    )
    (net (code "264") (name "Net-(U21-RefIO)") (class "Default")
      (node (ref "C74") (pin "2") (pinfunction "2_2") (pintype "passive"))
      (node (ref "U21") (pin "17") (pinfunction "RefIO_17") (pintype "power_in"))
    )
    (net (code "265") (name "Net-(U22-IPBS)") (class "Default")
      (node (ref "C78") (pin "2") (pinfunction "2_2") (pintype "passive"))
      (node (ref "U22") (pin "8") (pinfunction "IPBS_8") (pintype "input"))
    )
    (net (code "266") (name "Net-(U22-VREF)") (class "Default")
      (node (ref "C77") (pin "2") (pinfunction "2_2") (pintype "passive"))
      (node (ref "U22") (pin "7") (pinfunction "VREF_7") (pintype "output"))
    )
    (net (code "267") (name "Net-(U23-R_EXT)") (class "Default")
      (node (ref "R9") (pin "2") (pinfunction "2_2") (pintype "passive"))
      (node (ref "U23") (pin "15") (pinfunction "R_EXT_15") (pintype "passive"))
    )
    (net (code "268") (name "unconnected-(P3-PadA51)") (class "Default")
      (node (ref "P3") (pin "A51") (pinfunction "A51_A51") (pintype "passive"))
    )
    (net (code "269") (name "unconnected-(P3-PadA52)") (class "Default")
      (node (ref "P3") (pin "A52") (pinfunction "A52_A52") (pintype "passive"))
    )
    (net (code "270") (name "unconnected-(P3-PadA53)") (class "Default")
      (node (ref "P3") (pin "A53") (pinfunction "A53_A53") (pintype "passive"))
    )
    (net (code "271") (name "unconnected-(P3-PadA54)") (class "Default")
      (node (ref "P3") (pin "A54") (pinfunction "A54_A54") (pintype "passive"))
    )
    (net (code "272") (name "unconnected-(P3-PadA55)") (class "Default")
      (node (ref "P3") (pin "A55") (pinfunction "A55_A55") (pintype "passive"))
    )
    (net (code "273") (name "unconnected-(P3-PadA56)") (class "Default")
      (node (ref "P3") (pin "A56") (pinfunction "A56_A56") (pintype "passive"))
    )
    (net (code "274") (name "unconnected-(P3-PadB51)") (class "Default")
      (node (ref "P3") (pin "B51") (pinfunction "B51_B51") (pintype "passive"))
    )
    (net (code "275") (name "unconnected-(P3-PadB52)") (class "Default")
      (node (ref "P3") (pin "B52") (pinfunction "B52_B52") (pintype "passive"))
    )
    (net (code "276") (name "unconnected-(P3-PadB53)") (class "Default")
      (node (ref "P3") (pin "B53") (pinfunction "B53_B53") (pintype "passive"))
    )
    (net (code "277") (name "unconnected-(P3-PadB54)") (class "Default")
      (node (ref "P3") (pin "B54") (pinfunction "B54_B54") (pintype "passive"))
    )
    (net (code "278") (name "unconnected-(P3-PadB55)") (class "Default")
      (node (ref "P3") (pin "B55") (pinfunction "B55_B55") (pintype "passive"))
    )
    (net (code "279") (name "unconnected-(P3-PadB56)") (class "Default")
      (node (ref "P3") (pin "B56") (pinfunction "B56_B56") (pintype "passive"))
    )
    (net (code "280") (name "unconnected-(U21-NC-Pad19)") (class "Default")
      (node (ref "U21") (pin "19") (pinfunction "NC_19") (pintype "power_in"))
    )
    (net (code "281") (name "unconnected-(U21-Reserved-Pad23)") (class "Default")
      (node (ref "U21") (pin "23") (pinfunction "Reserved_23") (pintype "power_in"))
    )
    (net (code "282") (name "unconnected-(U21-Sleep-Pad15)") (class "Default")
      (node (ref "U21") (pin "15") (pinfunction "Sleep_15") (pintype "power_in"))
    )
    (net (code "283") (name "unconnected-(U22-OPBS-Pad9)") (class "Default")
      (node (ref "U22") (pin "9") (pinfunction "OPBS_9") (pintype "output"))
    )
    (net (code "284") (name "unconnected-(U23-SDO-Pad14)") (class "Default")
      (node (ref "U23") (pin "14") (pinfunction "SDO_14") (pintype "passive"))
    )
  )
)
